# mainboard_v03.net
KiCad netlist of a schematic drawn in EAGLE
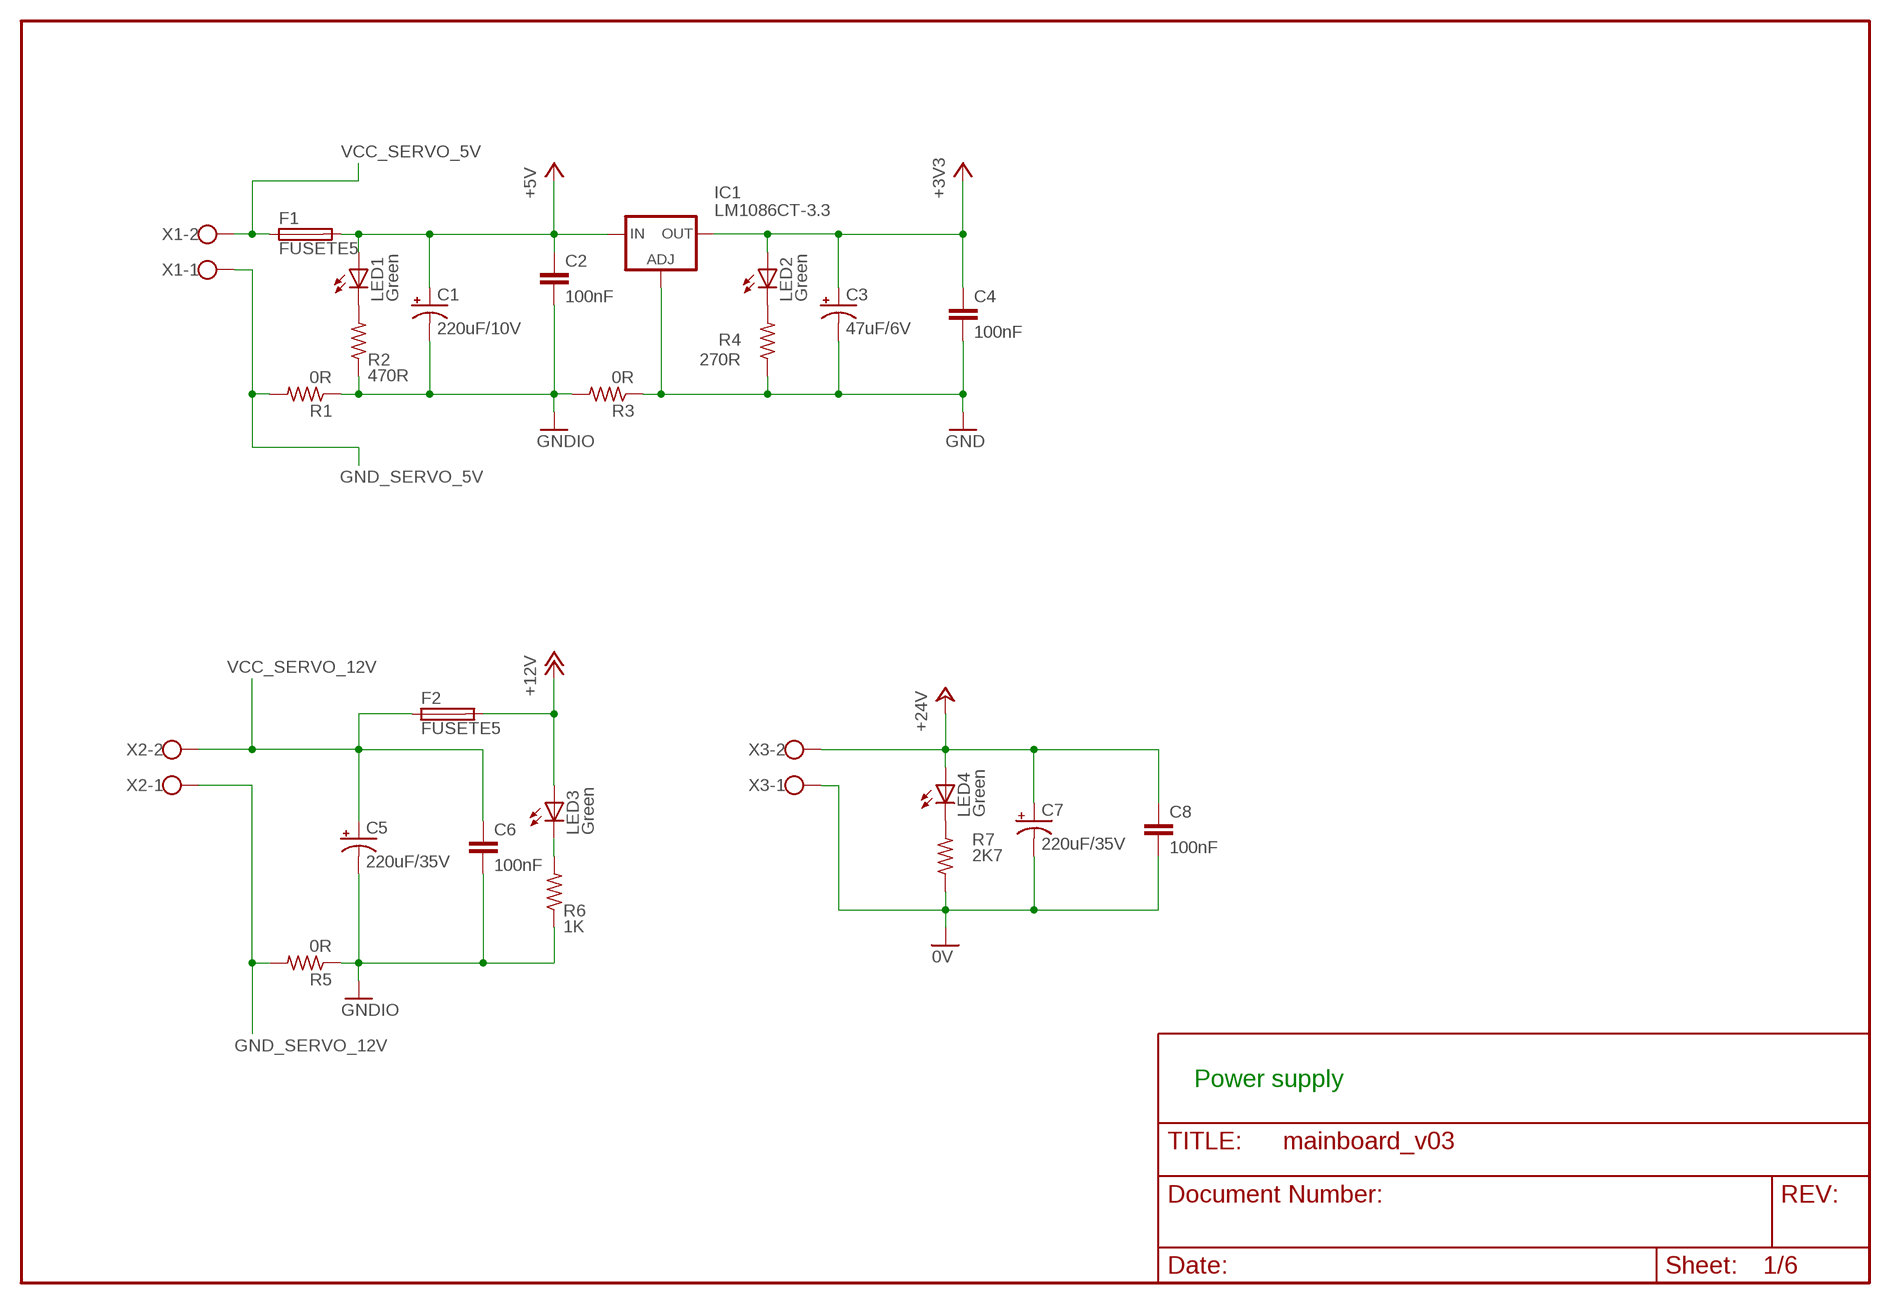
[diagram p0: schematic, sheet 1]
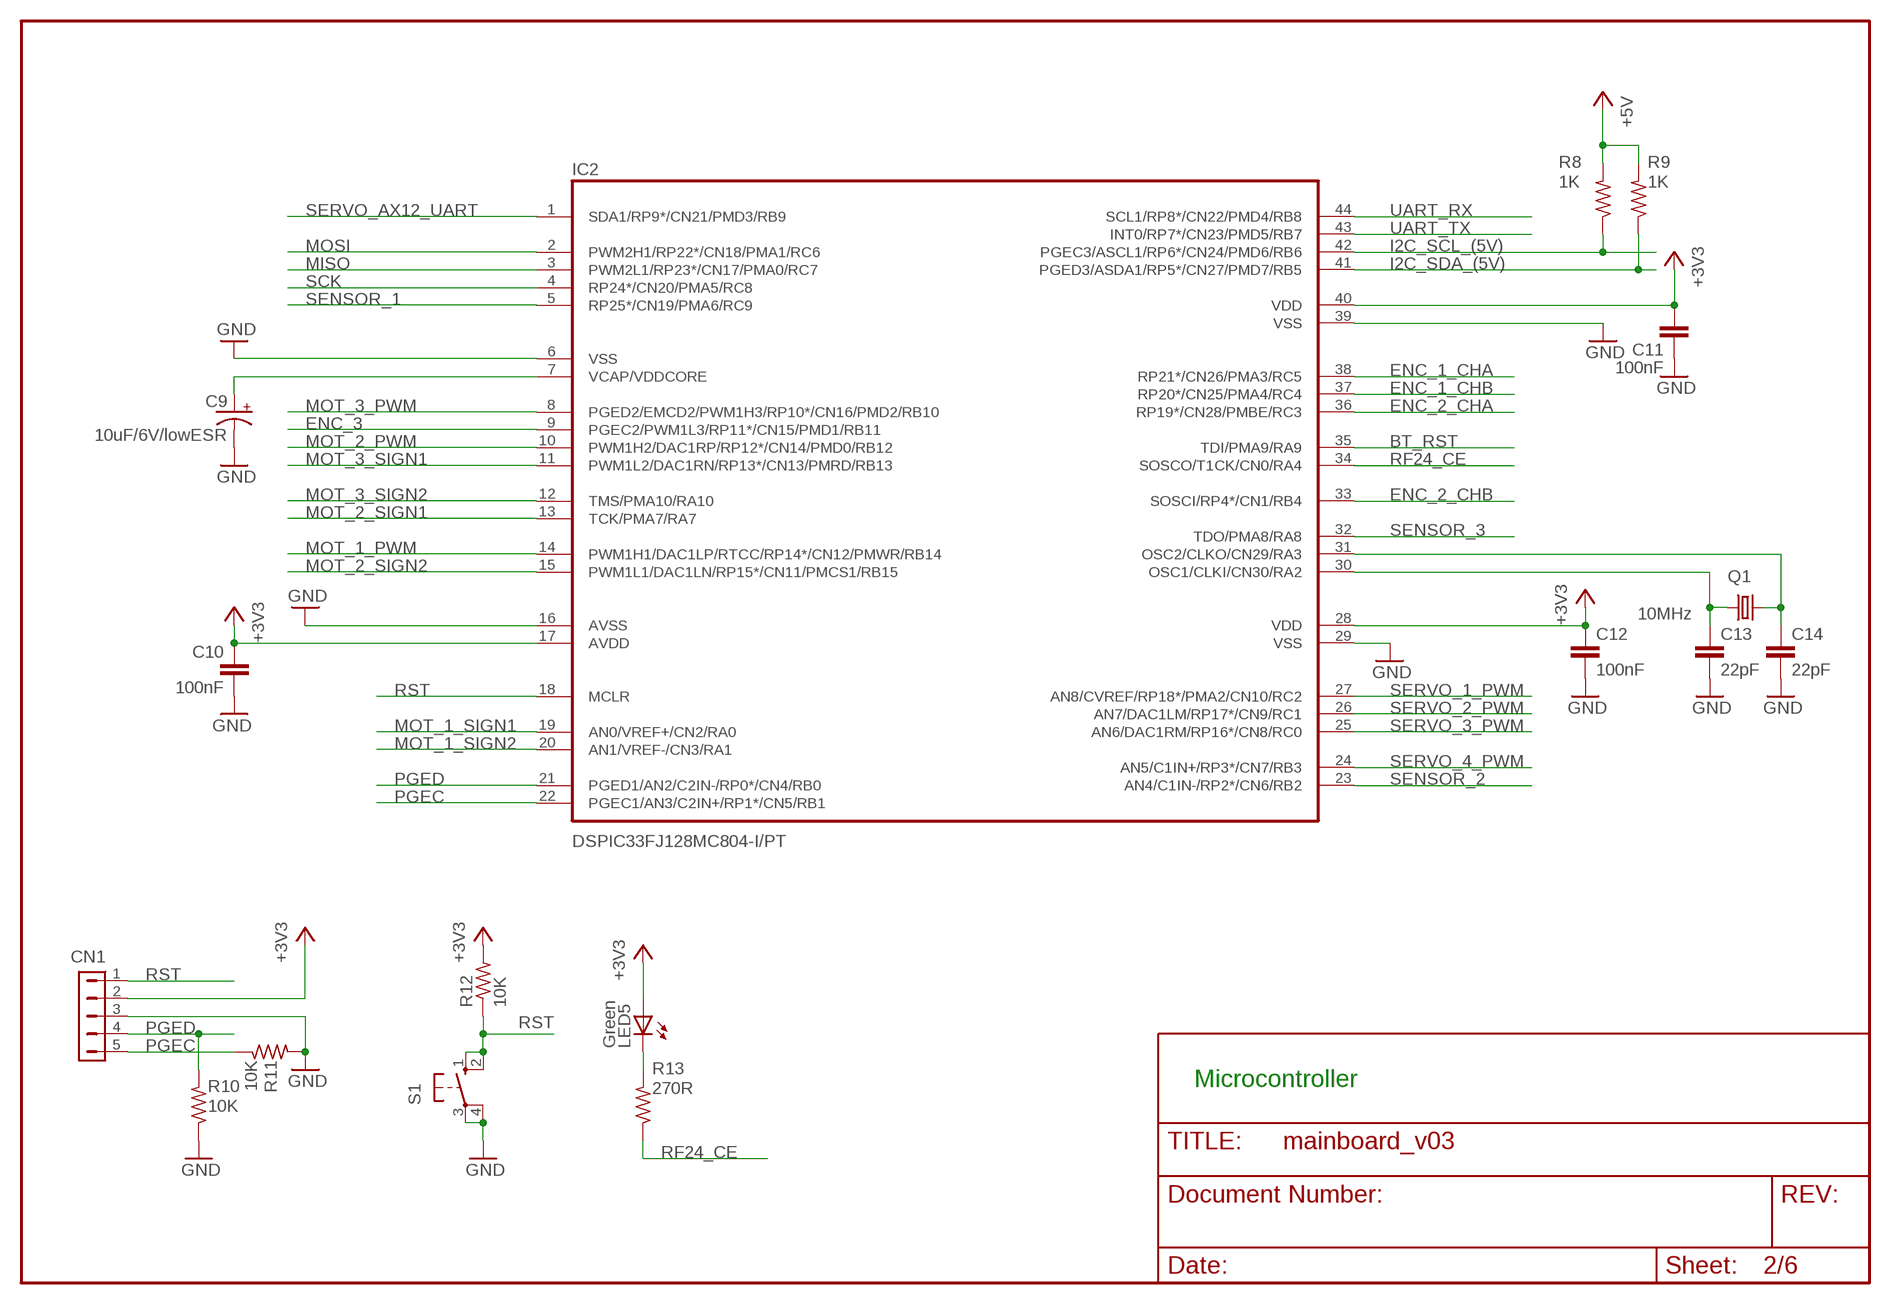
[diagram p1: schematic, sheet 2]
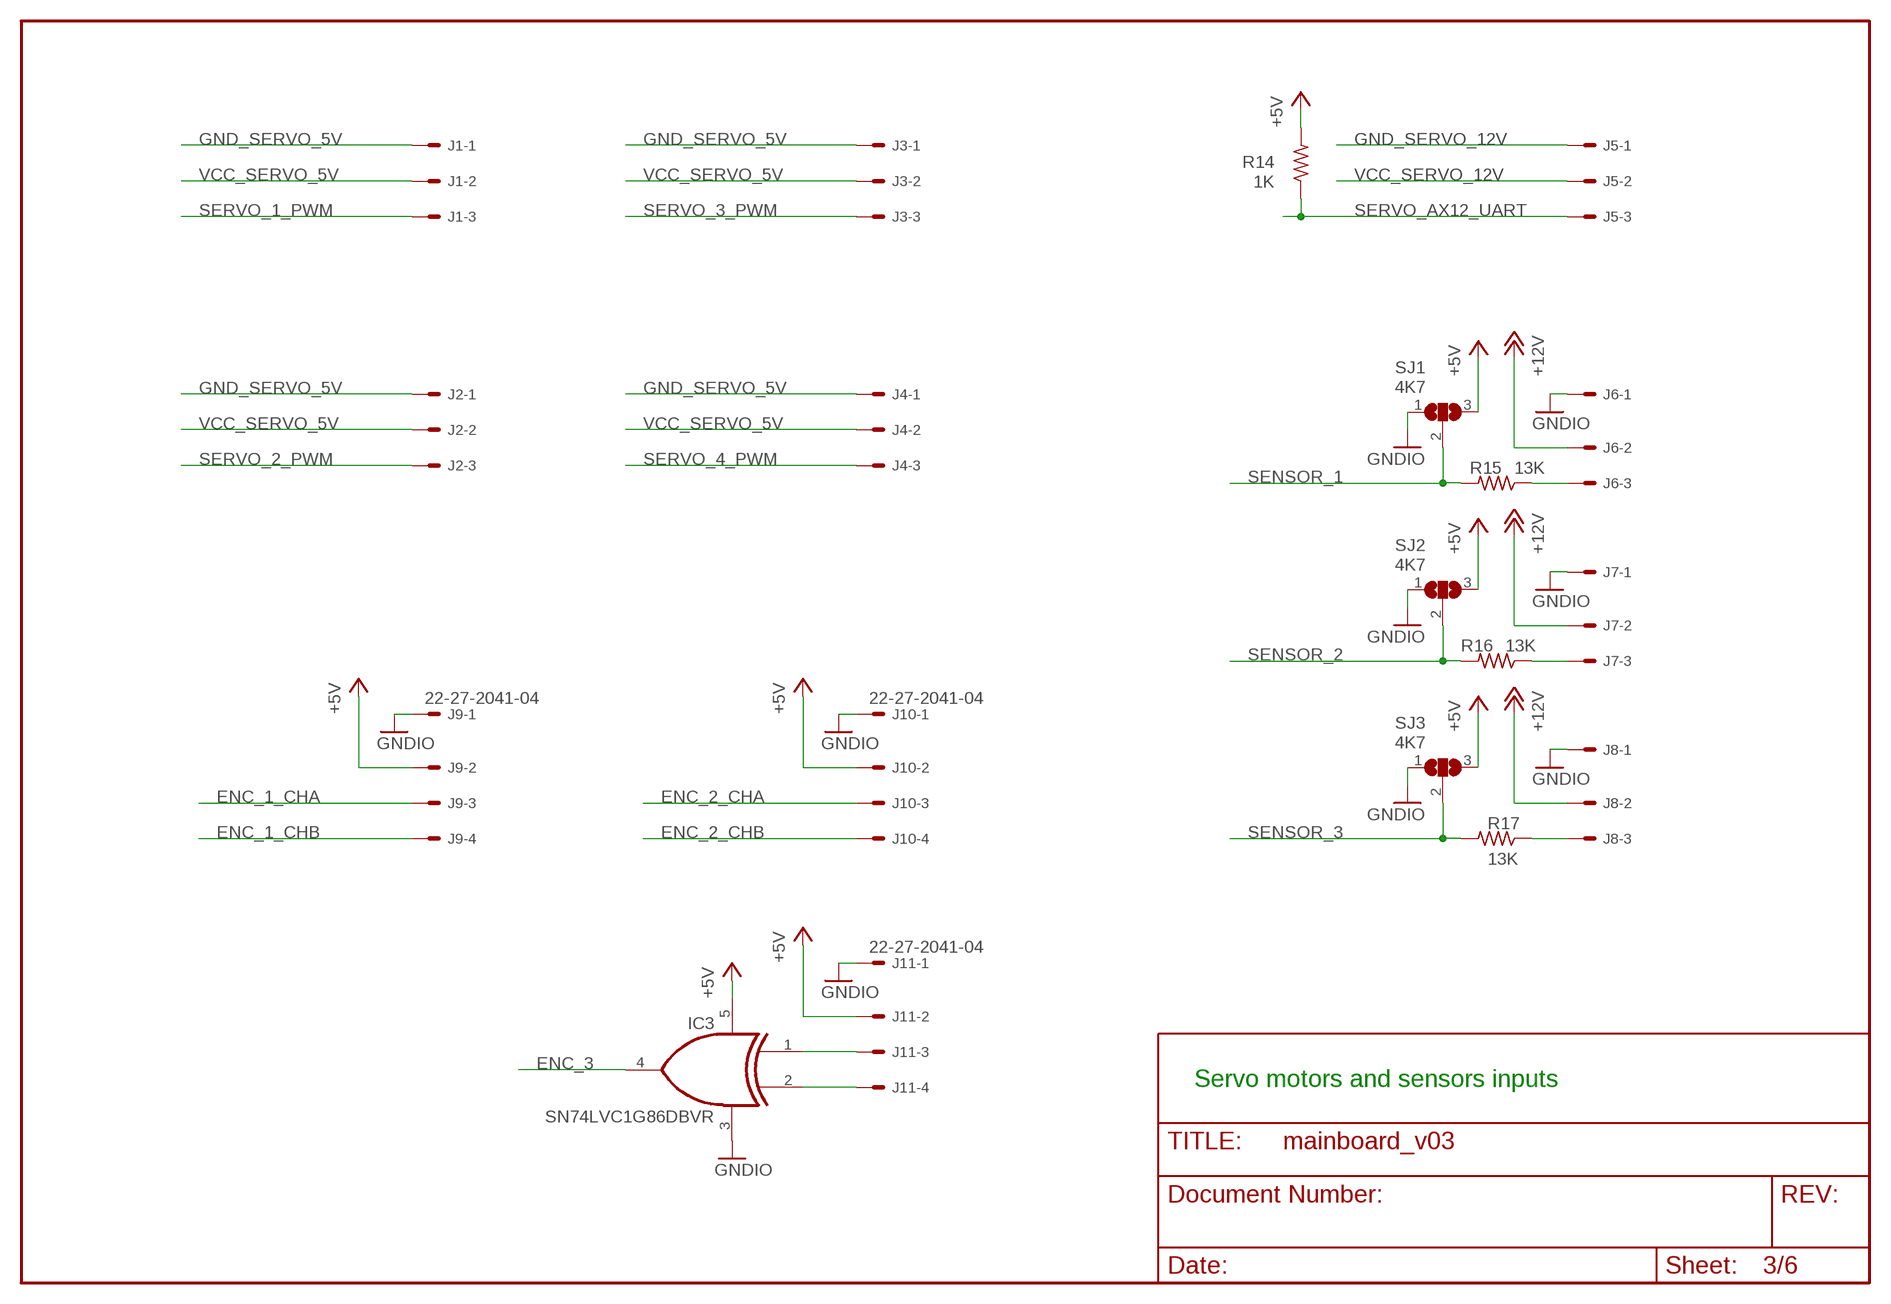
[diagram p2: schematic, sheet 3]
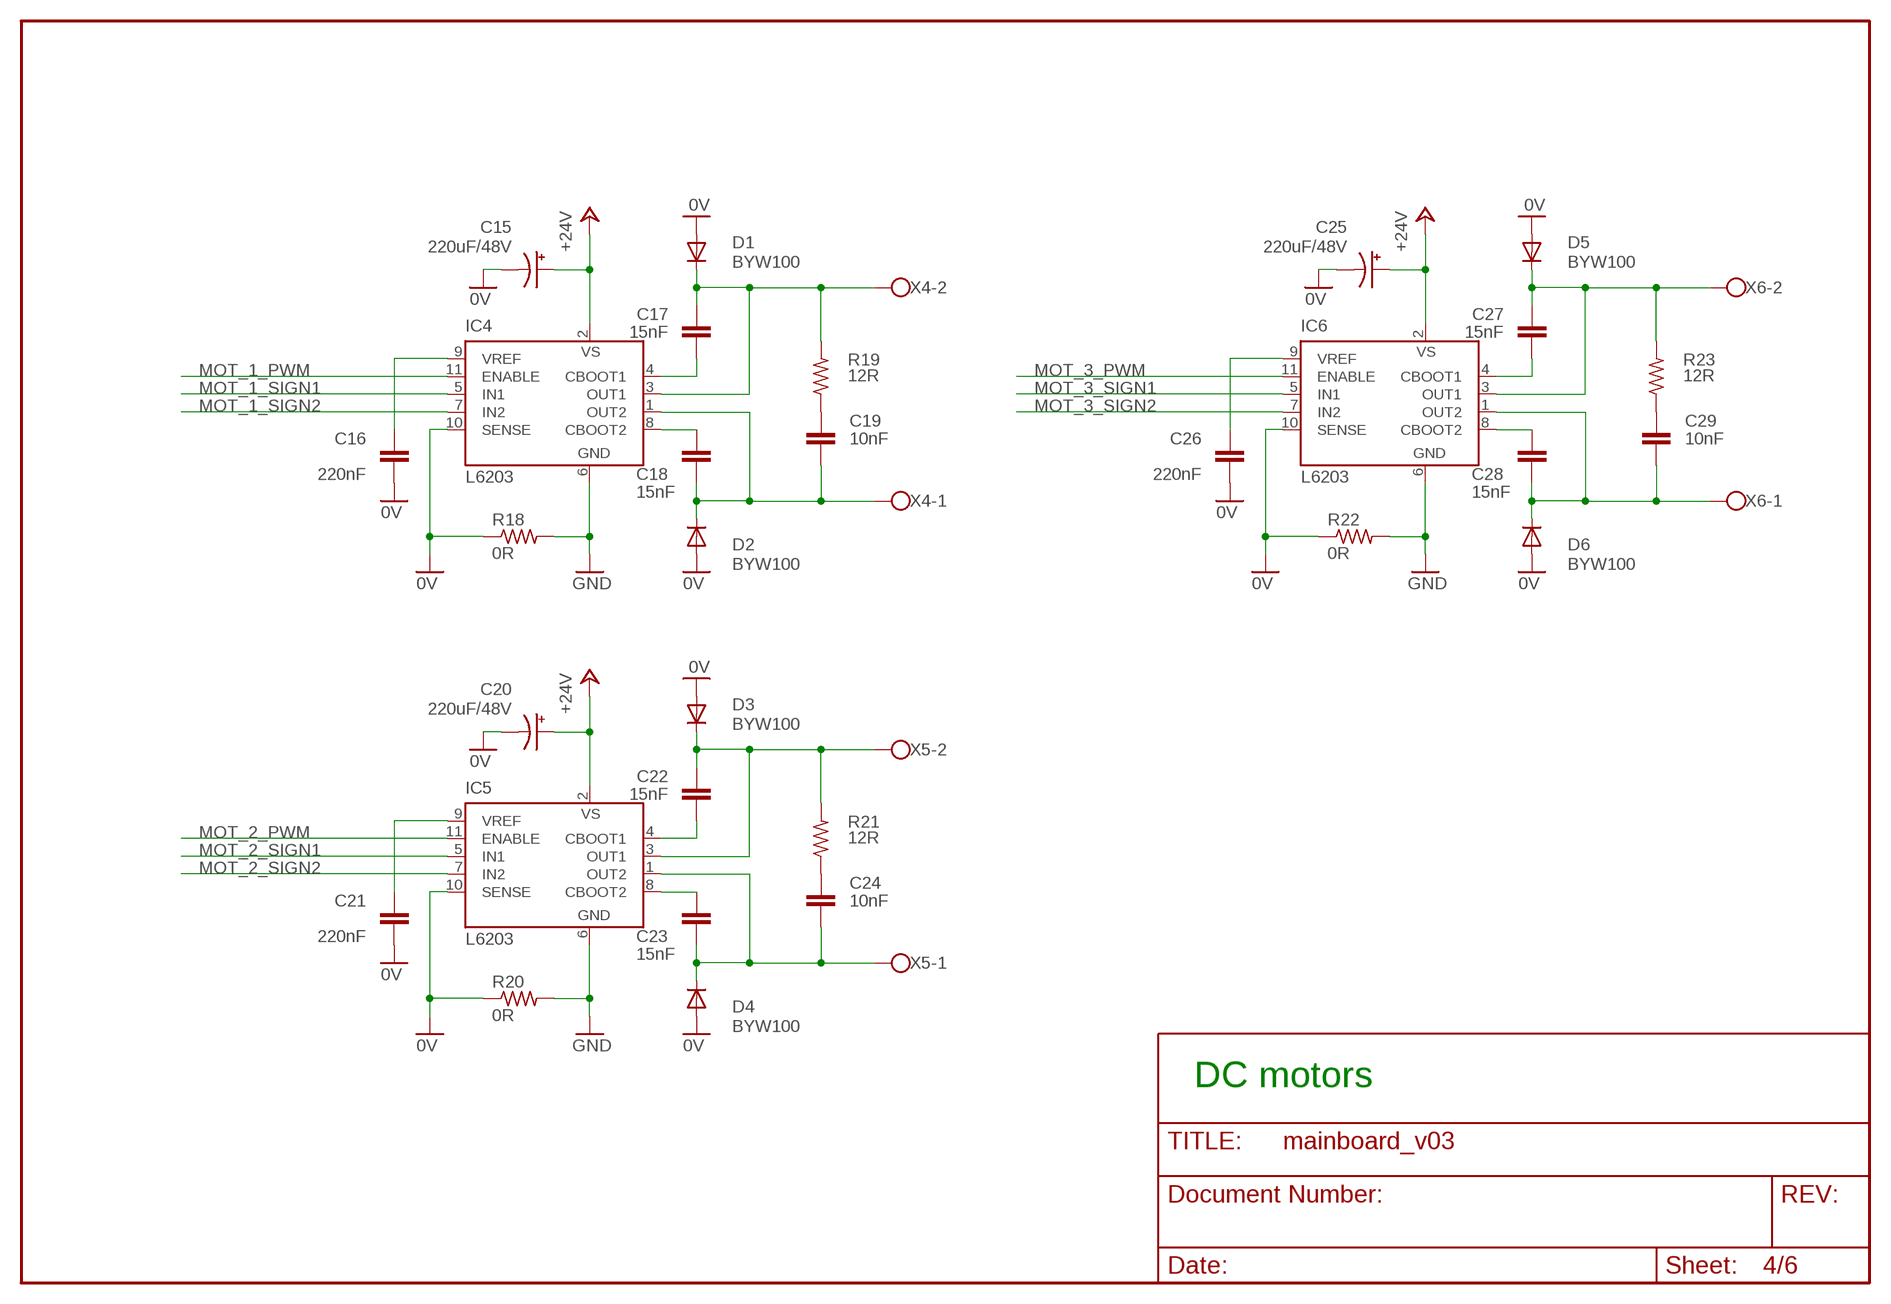
[diagram p3: schematic, sheet 4]
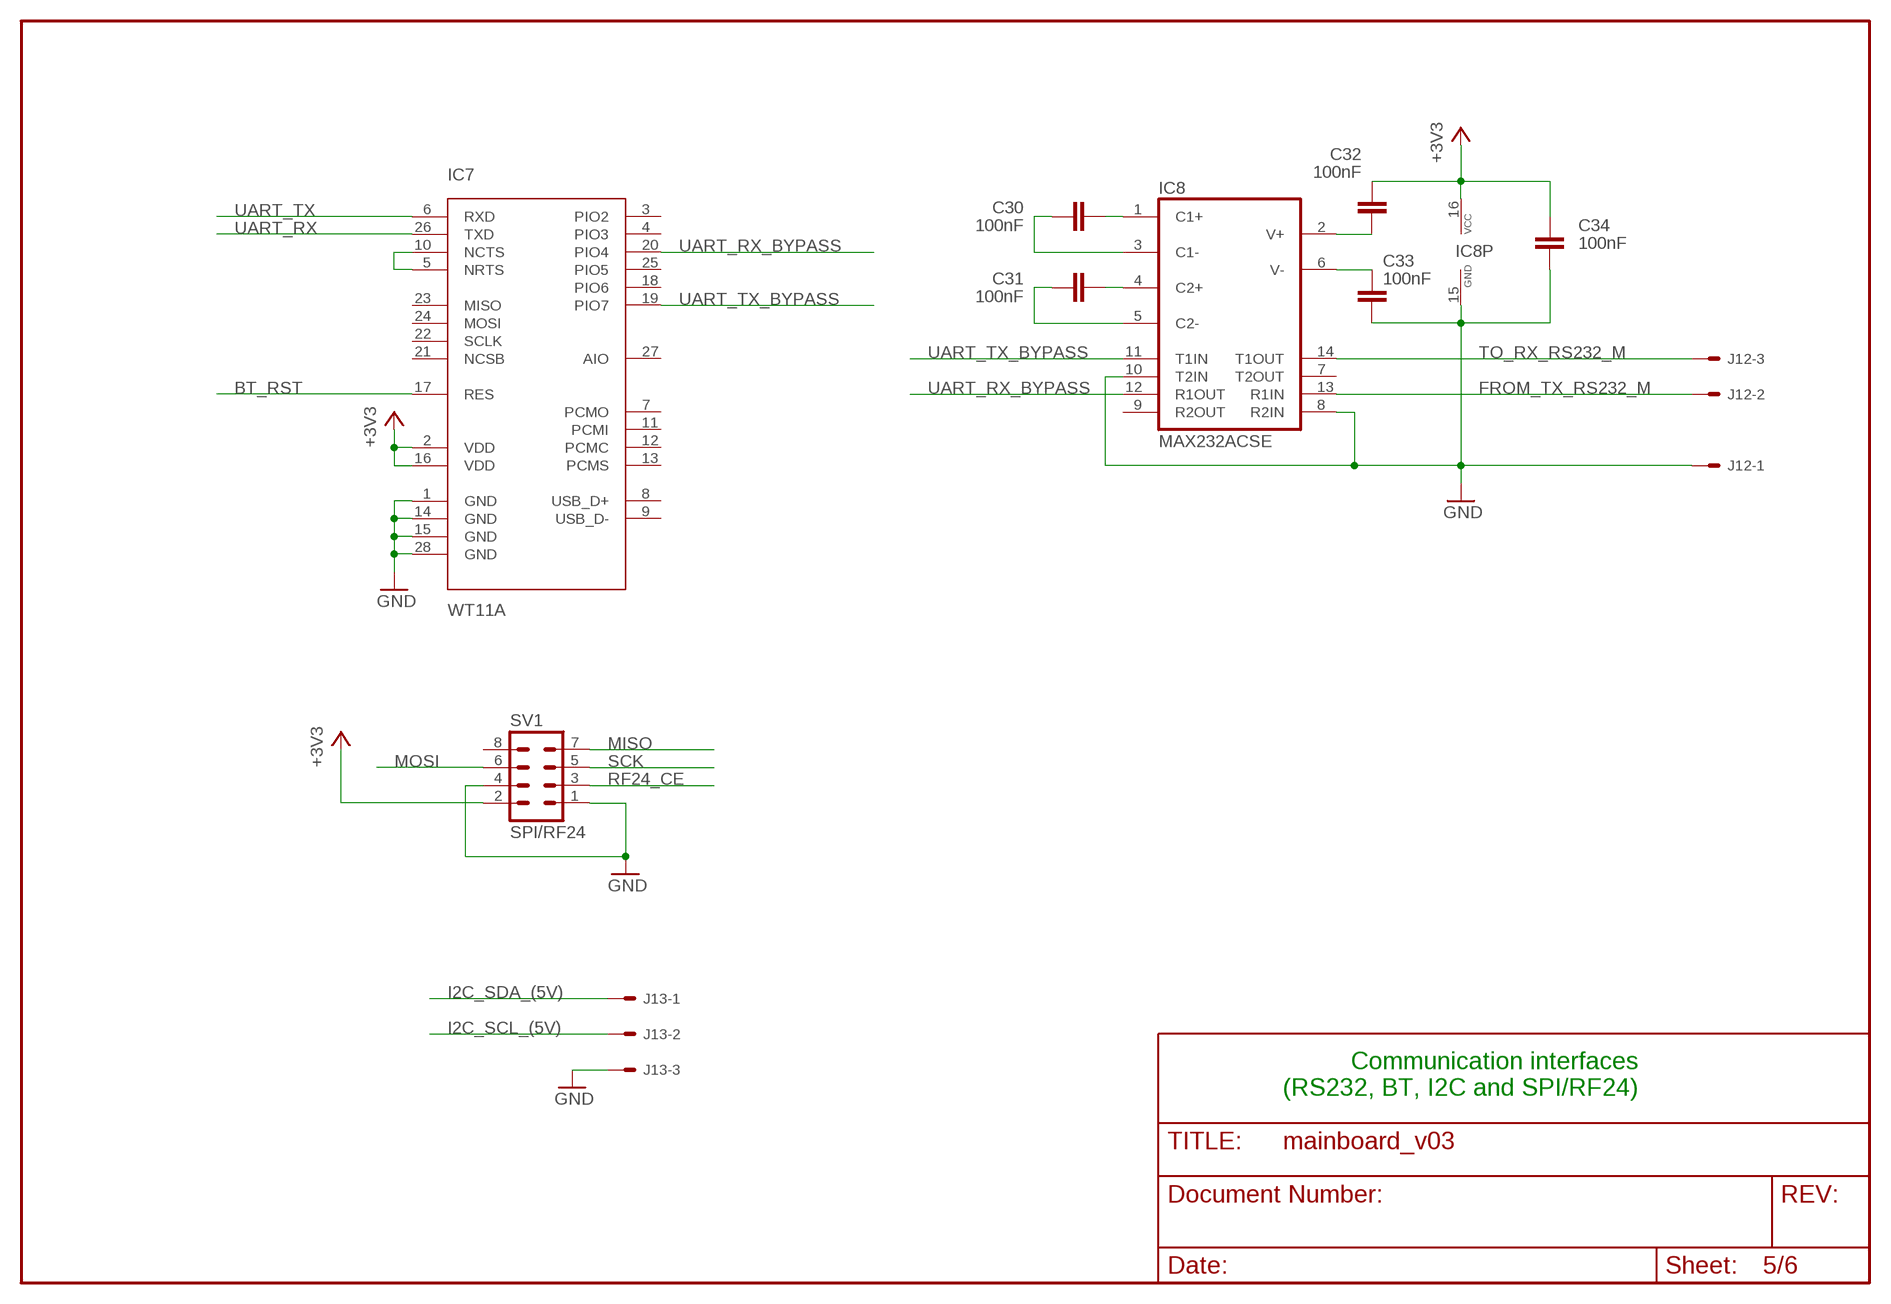
[diagram p4: schematic, sheet 5]
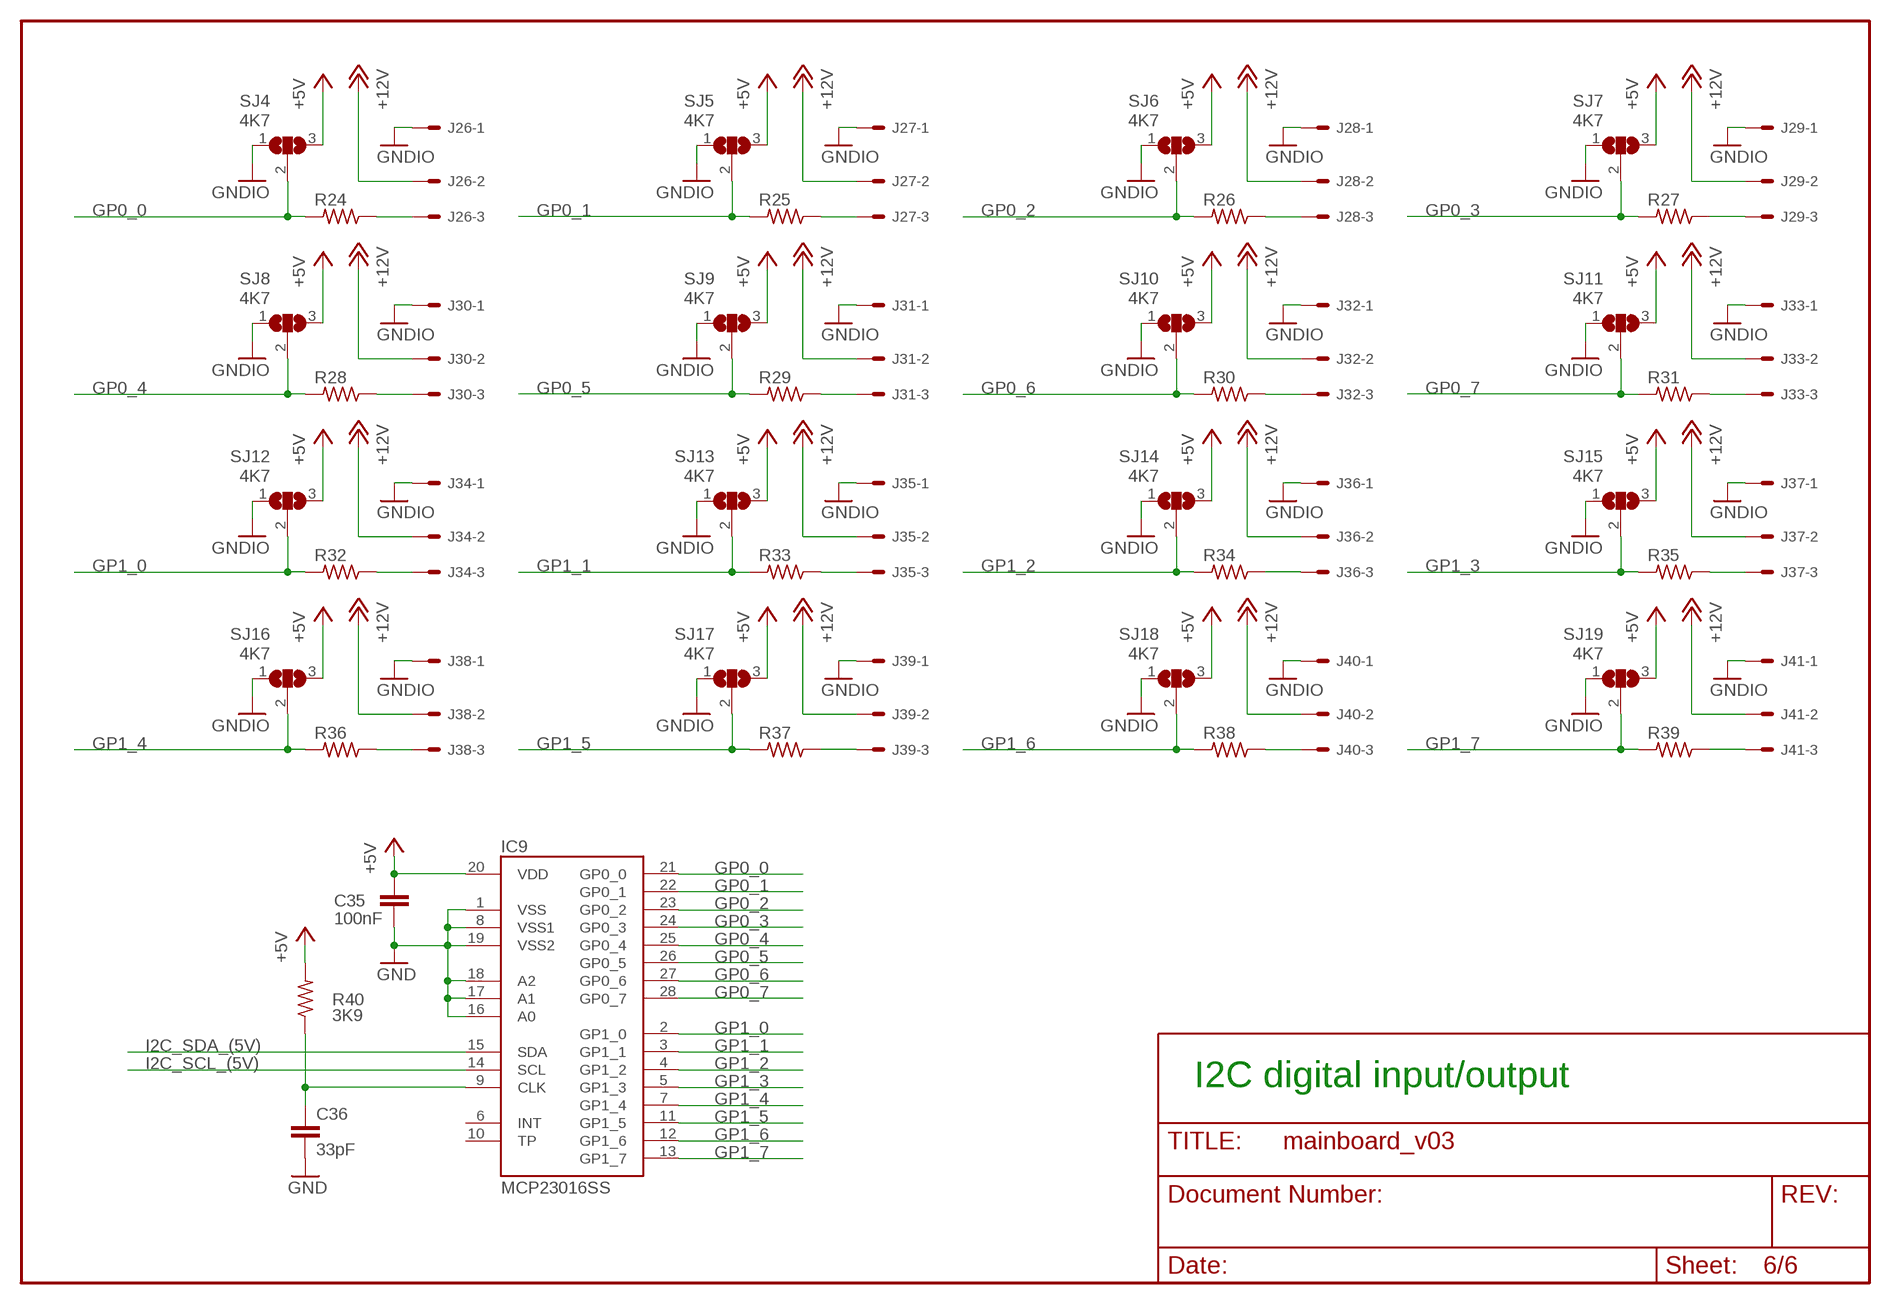
[diagram p5: schematic, sheet 6]

(export (version "E")
  (design (tool "Eeschema 10.0.6"))
  (components
    (comp (ref "C15")
      (value "220uF/48V")
      (footprint "eagle-import:E3,5-10")
      (libsource (lib "eagle-import") (part "CPOL-USE3.5-10"))
    )
    (comp (ref "C16")
      (value "220nF")
      (footprint "eagle-import:C0805")
      (libsource (lib "eagle-import") (part "C-EUC0805"))
    )
    (comp (ref "C17")
      (value "15nF")
      (footprint "eagle-import:C0805")
      (libsource (lib "eagle-import") (part "C-EUC0805"))
    )
    (comp (ref "C18")
      (value "15nF")
      (footprint "eagle-import:C0805")
      (libsource (lib "eagle-import") (part "C-EUC0805"))
    )
    (comp (ref "C19")
      (value "10nF")
      (footprint "eagle-import:C0805")
      (libsource (lib "eagle-import") (part "C-EUC0805"))
    )
    (comp (ref "C20")
      (value "220uF/48V")
      (footprint "eagle-import:E3,5-10")
      (libsource (lib "eagle-import") (part "CPOL-USE3.5-10"))
    )
    (comp (ref "C21")
      (value "220nF")
      (footprint "eagle-import:C0805")
      (libsource (lib "eagle-import") (part "C-EUC0805"))
    )
    (comp (ref "C22")
      (value "15nF")
      (footprint "eagle-import:C0805")
      (libsource (lib "eagle-import") (part "C-EUC0805"))
    )
    (comp (ref "C23")
      (value "15nF")
      (footprint "eagle-import:C0805")
      (libsource (lib "eagle-import") (part "C-EUC0805"))
    )
    (comp (ref "C24")
      (value "10nF")
      (footprint "eagle-import:C0805")
      (libsource (lib "eagle-import") (part "C-EUC0805"))
    )
    (comp (ref "C25")
      (value "220uF/48V")
      (footprint "eagle-import:E3,5-10")
      (libsource (lib "eagle-import") (part "CPOL-USE3.5-10"))
    )
    (comp (ref "C26")
      (value "220nF")
      (footprint "eagle-import:C0805")
      (libsource (lib "eagle-import") (part "C-EUC0805"))
    )
    (comp (ref "C27")
      (value "15nF")
      (footprint "eagle-import:C0805")
      (libsource (lib "eagle-import") (part "C-EUC0805"))
    )
    (comp (ref "C28")
      (value "15nF")
      (footprint "eagle-import:C0805")
      (libsource (lib "eagle-import") (part "C-EUC0805"))
    )
    (comp (ref "C29")
      (value "10nF")
      (footprint "eagle-import:C0805")
      (libsource (lib "eagle-import") (part "C-EUC0805"))
    )
    (comp (ref "D1")
      (value "BYW100")
      (footprint "eagle-import:F126-10")
      (libsource (lib "eagle-import") (part "BYW100"))
    )
    (comp (ref "D2")
      (value "BYW100")
      (footprint "eagle-import:F126-10")
      (libsource (lib "eagle-import") (part "BYW100"))
    )
    (comp (ref "D3")
      (value "BYW100")
      (footprint "eagle-import:F126-10")
      (libsource (lib "eagle-import") (part "BYW100"))
    )
    (comp (ref "D4")
      (value "BYW100")
      (footprint "eagle-import:F126-10")
      (libsource (lib "eagle-import") (part "BYW100"))
    )
    (comp (ref "D5")
      (value "BYW100")
      (footprint "eagle-import:F126-10")
      (libsource (lib "eagle-import") (part "BYW100"))
    )
    (comp (ref "D6")
      (value "BYW100")
      (footprint "eagle-import:F126-10")
      (libsource (lib "eagle-import") (part "BYW100"))
    )
    (comp (ref "IC4")
      (value "L6203")
      (footprint "eagle-import:MULTIWATT-11")
      (libsource (lib "eagle-import") (part "L6203"))
    )
    (comp (ref "IC5")
      (value "L6203")
      (footprint "eagle-import:MULTIWATT-11")
      (libsource (lib "eagle-import") (part "L6203"))
    )
    (comp (ref "IC6")
      (value "L6203")
      (footprint "eagle-import:MULTIWATT-11")
      (libsource (lib "eagle-import") (part "L6203"))
    )
    (comp (ref "R18")
      (value "0R")
      (footprint "eagle-import:M0805")
      (libsource (lib "eagle-import") (part "R-US_M0805"))
    )
    (comp (ref "R19")
      (value "12R")
      (footprint "eagle-import:M0805")
      (libsource (lib "eagle-import") (part "R-US_M0805"))
    )
    (comp (ref "R20")
      (value "0R")
      (footprint "eagle-import:M0805")
      (libsource (lib "eagle-import") (part "R-US_M0805"))
    )
    (comp (ref "R21")
      (value "12R")
      (footprint "eagle-import:M0805")
      (libsource (lib "eagle-import") (part "R-US_M0805"))
    )
    (comp (ref "R22")
      (value "0R")
      (footprint "eagle-import:M0805")
      (libsource (lib "eagle-import") (part "R-US_M0805"))
    )
    (comp (ref "R23")
      (value "12R")
      (footprint "eagle-import:M0805")
      (libsource (lib "eagle-import") (part "R-US_M0805"))
    )
    (comp (ref "X4")
      (value "W237-02P")
      (footprint "eagle-import:W237-132")
      (libsource (lib "eagle-import") (part "W237-02P"))
    )
    (comp (ref "X5")
      (value "W237-02P")
      (footprint "eagle-import:W237-132")
      (libsource (lib "eagle-import") (part "W237-02P"))
    )
    (comp (ref "X6")
      (value "W237-02P")
      (footprint "eagle-import:W237-132")
      (libsource (lib "eagle-import") (part "W237-02P"))
    )
    (comp (ref "IC3")
      (value "SN74LVC1G86DBVR")
      (footprint "eagle-import:SOT23-5")
      (libsource (lib "eagle-import") (part "741G86DBVAHC"))
    )
    (comp (ref "J1")
      (value "22-27-2031-03")
      (footprint "eagle-import:6410-03")
      (libsource (lib "eagle-import") (part "22-?-0327-2031"))
    )
    (comp (ref "J2")
      (value "22-27-2031-03")
      (footprint "eagle-import:6410-03")
      (libsource (lib "eagle-import") (part "22-?-0327-2031"))
    )
    (comp (ref "J3")
      (value "22-27-2031-03")
      (footprint "eagle-import:6410-03")
      (libsource (lib "eagle-import") (part "22-?-0327-2031"))
    )
    (comp (ref "J4")
      (value "22-27-2031-03")
      (footprint "eagle-import:6410-03")
      (libsource (lib "eagle-import") (part "22-?-0327-2031"))
    )
    (comp (ref "J5")
      (value "22-27-2031-03")
      (footprint "eagle-import:6410-03")
      (libsource (lib "eagle-import") (part "22-?-0327-2031"))
    )
    (comp (ref "J6")
      (value "22-27-2031-03")
      (footprint "eagle-import:6410-03")
      (libsource (lib "eagle-import") (part "22-?-0327-2031"))
    )
    (comp (ref "J7")
      (value "22-27-2031-03")
      (footprint "eagle-import:6410-03")
      (libsource (lib "eagle-import") (part "22-?-0327-2031"))
    )
    (comp (ref "J8")
      (value "22-27-2031-03")
      (footprint "eagle-import:6410-03")
      (libsource (lib "eagle-import") (part "22-?-0327-2031"))
    )
    (comp (ref "J9")
      (value "22-27-2041-04")
      (footprint "eagle-import:6410-04")
      (libsource (lib "eagle-import") (part "22-?-0427-2041"))
    )
    (comp (ref "J10")
      (value "22-27-2041-04")
      (footprint "eagle-import:6410-04")
      (libsource (lib "eagle-import") (part "22-?-0427-2041"))
    )
    (comp (ref "J11")
      (value "22-27-2041-04")
      (footprint "eagle-import:6410-04")
      (libsource (lib "eagle-import") (part "22-?-0427-2041"))
    )
    (comp (ref "R14")
      (value "1K")
      (footprint "eagle-import:R0805")
      (libsource (lib "eagle-import") (part "R-US_R0805"))
    )
    (comp (ref "R15")
      (value "13K")
      (footprint "eagle-import:R0805")
      (libsource (lib "eagle-import") (part "R-US_R0805"))
    )
    (comp (ref "R16")
      (value "13K")
      (footprint "eagle-import:R0805")
      (libsource (lib "eagle-import") (part "R-US_R0805"))
    )
    (comp (ref "R17")
      (value "13K")
      (footprint "eagle-import:R0805")
      (libsource (lib "eagle-import") (part "R-US_R0805"))
    )
    (comp (ref "SJ1")
      (value "4K7")
      (footprint "eagle-import:SJ_2")
      (libsource (lib "eagle-import") (part "SJ2W"))
    )
    (comp (ref "SJ2")
      (value "4K7")
      (footprint "eagle-import:SJ_2")
      (libsource (lib "eagle-import") (part "SJ2W"))
    )
    (comp (ref "SJ3")
      (value "4K7")
      (footprint "eagle-import:SJ_2")
      (libsource (lib "eagle-import") (part "SJ2W"))
    )
    (comp (ref "C30")
      (value "100nF")
      (footprint "eagle-import:C0603")
      (libsource (lib "eagle-import") (part "C-EUC0603"))
    )
    (comp (ref "C31")
      (value "100nF")
      (footprint "eagle-import:C0603")
      (libsource (lib "eagle-import") (part "C-EUC0603"))
    )
    (comp (ref "C32")
      (value "100nF")
      (footprint "eagle-import:C0603")
      (libsource (lib "eagle-import") (part "C-EUC0603"))
    )
    (comp (ref "C33")
      (value "100nF")
      (footprint "eagle-import:C0603")
      (libsource (lib "eagle-import") (part "C-EUC0603"))
    )
    (comp (ref "C34")
      (value "100nF")
      (footprint "eagle-import:C0603")
      (libsource (lib "eagle-import") (part "C-EUC0603"))
    )
    (comp (ref "IC7")
      (value "WT11A")
      (footprint "eagle-import:WT11")
      (libsource (lib "eagle-import") (part "WT11A"))
    )
    (comp (ref "IC8")
      (value "MAX232ACSE")
      (footprint "eagle-import:SO16")
      (libsource (lib "eagle-import") (part "MAX232SEAC"))
    )
    (comp (ref "J12")
      (value "22-27-2031-03")
      (footprint "eagle-import:6410-03")
      (libsource (lib "eagle-import") (part "22-?-0327-2031"))
    )
    (comp (ref "J13")
      (value "22-27-2031-03")
      (footprint "eagle-import:6410-03")
      (libsource (lib "eagle-import") (part "22-?-0327-2031"))
    )
    (comp (ref "SV1")
      (value "SPI/RF24")
      (footprint "eagle-import:MA04-2")
      (libsource (lib "eagle-import") (part "MA04-2"))
    )
    (comp (ref "C35")
      (value "100nF")
      (footprint "eagle-import:C0805")
      (libsource (lib "eagle-import") (part "C-EUC0805"))
    )
    (comp (ref "C36")
      (value "33pF")
      (footprint "eagle-import:C0805")
      (libsource (lib "eagle-import") (part "C-EUC0805"))
    )
    (comp (ref "IC9")
      (value "MCP23016SS")
      (footprint "eagle-import:SSOP28")
      (libsource (lib "eagle-import") (part "MCP23016SS"))
    )
    (comp (ref "J26")
      (value "22-27-2031-03")
      (footprint "eagle-import:6410-03")
      (libsource (lib "eagle-import") (part "22-?-0327-2031"))
    )
    (comp (ref "J27")
      (value "22-27-2031-03")
      (footprint "eagle-import:6410-03")
      (libsource (lib "eagle-import") (part "22-?-0327-2031"))
    )
    (comp (ref "J28")
      (value "22-27-2031-03")
      (footprint "eagle-import:6410-03")
      (libsource (lib "eagle-import") (part "22-?-0327-2031"))
    )
    (comp (ref "J29")
      (value "22-27-2031-03")
      (footprint "eagle-import:6410-03")
      (libsource (lib "eagle-import") (part "22-?-0327-2031"))
    )
    (comp (ref "J30")
      (value "22-27-2031-03")
      (footprint "eagle-import:6410-03")
      (libsource (lib "eagle-import") (part "22-?-0327-2031"))
    )
    (comp (ref "J31")
      (value "22-27-2031-03")
      (footprint "eagle-import:6410-03")
      (libsource (lib "eagle-import") (part "22-?-0327-2031"))
    )
    (comp (ref "J32")
      (value "22-27-2031-03")
      (footprint "eagle-import:6410-03")
      (libsource (lib "eagle-import") (part "22-?-0327-2031"))
    )
    (comp (ref "J33")
      (value "22-27-2031-03")
      (footprint "eagle-import:6410-03")
      (libsource (lib "eagle-import") (part "22-?-0327-2031"))
    )
    (comp (ref "J34")
      (value "22-27-2031-03")
      (footprint "eagle-import:6410-03")
      (libsource (lib "eagle-import") (part "22-?-0327-2031"))
    )
    (comp (ref "J35")
      (value "22-27-2031-03")
      (footprint "eagle-import:6410-03")
      (libsource (lib "eagle-import") (part "22-?-0327-2031"))
    )
    (comp (ref "J36")
      (value "22-27-2031-03")
      (footprint "eagle-import:6410-03")
      (libsource (lib "eagle-import") (part "22-?-0327-2031"))
    )
    (comp (ref "J37")
      (value "22-27-2031-03")
      (footprint "eagle-import:6410-03")
      (libsource (lib "eagle-import") (part "22-?-0327-2031"))
    )
    (comp (ref "J38")
      (value "22-27-2031-03")
      (footprint "eagle-import:6410-03")
      (libsource (lib "eagle-import") (part "22-?-0327-2031"))
    )
    (comp (ref "J39")
      (value "22-27-2031-03")
      (footprint "eagle-import:6410-03")
      (libsource (lib "eagle-import") (part "22-?-0327-2031"))
    )
    (comp (ref "J40")
      (value "22-27-2031-03")
      (footprint "eagle-import:6410-03")
      (libsource (lib "eagle-import") (part "22-?-0327-2031"))
    )
    (comp (ref "J41")
      (value "22-27-2031-03")
      (footprint "eagle-import:6410-03")
      (libsource (lib "eagle-import") (part "22-?-0327-2031"))
    )
    (comp (ref "R24")
      (value "R-US_R0805")
      (footprint "eagle-import:R0805")
      (libsource (lib "eagle-import") (part "R-US_R0805"))
    )
    (comp (ref "R25")
      (value "R-US_R0805")
      (footprint "eagle-import:R0805")
      (libsource (lib "eagle-import") (part "R-US_R0805"))
    )
    (comp (ref "R26")
      (value "R-US_R0805")
      (footprint "eagle-import:R0805")
      (libsource (lib "eagle-import") (part "R-US_R0805"))
    )
    (comp (ref "R27")
      (value "R-US_R0805")
      (footprint "eagle-import:R0805")
      (libsource (lib "eagle-import") (part "R-US_R0805"))
    )
    (comp (ref "R28")
      (value "R-US_R0805")
      (footprint "eagle-import:R0805")
      (libsource (lib "eagle-import") (part "R-US_R0805"))
    )
    (comp (ref "R29")
      (value "R-US_R0805")
      (footprint "eagle-import:R0805")
      (libsource (lib "eagle-import") (part "R-US_R0805"))
    )
    (comp (ref "R30")
      (value "R-US_R0805")
      (footprint "eagle-import:R0805")
      (libsource (lib "eagle-import") (part "R-US_R0805"))
    )
    (comp (ref "R31")
      (value "R-US_R0805")
      (footprint "eagle-import:R0805")
      (libsource (lib "eagle-import") (part "R-US_R0805"))
    )
    (comp (ref "R32")
      (value "R-US_R0805")
      (footprint "eagle-import:R0805")
      (libsource (lib "eagle-import") (part "R-US_R0805"))
    )
    (comp (ref "R33")
      (value "R-US_R0805")
      (footprint "eagle-import:R0805")
      (libsource (lib "eagle-import") (part "R-US_R0805"))
    )
    (comp (ref "R34")
      (value "R-US_R0805")
      (footprint "eagle-import:R0805")
      (libsource (lib "eagle-import") (part "R-US_R0805"))
    )
    (comp (ref "R35")
      (value "R-US_R0805")
      (footprint "eagle-import:R0805")
      (libsource (lib "eagle-import") (part "R-US_R0805"))
    )
    (comp (ref "R36")
      (value "R-US_R0805")
      (footprint "eagle-import:R0805")
      (libsource (lib "eagle-import") (part "R-US_R0805"))
    )
    (comp (ref "R37")
      (value "R-US_R0805")
      (footprint "eagle-import:R0805")
      (libsource (lib "eagle-import") (part "R-US_R0805"))
    )
    (comp (ref "R38")
      (value "R-US_R0805")
      (footprint "eagle-import:R0805")
      (libsource (lib "eagle-import") (part "R-US_R0805"))
    )
    (comp (ref "R39")
      (value "R-US_R0805")
      (footprint "eagle-import:R0805")
      (libsource (lib "eagle-import") (part "R-US_R0805"))
    )
    (comp (ref "R40")
      (value "3K9")
      (footprint "eagle-import:R0805")
      (libsource (lib "eagle-import") (part "R-US_R0805"))
    )
    (comp (ref "SJ4")
      (value "4K7")
      (footprint "eagle-import:SJ_2")
      (libsource (lib "eagle-import") (part "SJ2W"))
    )
    (comp (ref "SJ5")
      (value "4K7")
      (footprint "eagle-import:SJ_2")
      (libsource (lib "eagle-import") (part "SJ2W"))
    )
    (comp (ref "SJ6")
      (value "4K7")
      (footprint "eagle-import:SJ_2")
      (libsource (lib "eagle-import") (part "SJ2W"))
    )
    (comp (ref "SJ7")
      (value "4K7")
      (footprint "eagle-import:SJ_2")
      (libsource (lib "eagle-import") (part "SJ2W"))
    )
    (comp (ref "SJ8")
      (value "4K7")
      (footprint "eagle-import:SJ_2")
      (libsource (lib "eagle-import") (part "SJ2W"))
    )
    (comp (ref "SJ9")
      (value "4K7")
      (footprint "eagle-import:SJ_2")
      (libsource (lib "eagle-import") (part "SJ2W"))
    )
    (comp (ref "SJ10")
      (value "4K7")
      (footprint "eagle-import:SJ_2")
      (libsource (lib "eagle-import") (part "SJ2W"))
    )
    (comp (ref "SJ11")
      (value "4K7")
      (footprint "eagle-import:SJ_2")
      (libsource (lib "eagle-import") (part "SJ2W"))
    )
    (comp (ref "SJ12")
      (value "4K7")
      (footprint "eagle-import:SJ_2")
      (libsource (lib "eagle-import") (part "SJ2W"))
    )
    (comp (ref "SJ13")
      (value "4K7")
      (footprint "eagle-import:SJ_2")
      (libsource (lib "eagle-import") (part "SJ2W"))
    )
    (comp (ref "SJ14")
      (value "4K7")
      (footprint "eagle-import:SJ_2")
      (libsource (lib "eagle-import") (part "SJ2W"))
    )
    (comp (ref "SJ15")
      (value "4K7")
      (footprint "eagle-import:SJ_2")
      (libsource (lib "eagle-import") (part "SJ2W"))
    )
    (comp (ref "SJ16")
      (value "4K7")
      (footprint "eagle-import:SJ_2")
      (libsource (lib "eagle-import") (part "SJ2W"))
    )
    (comp (ref "SJ17")
      (value "4K7")
      (footprint "eagle-import:SJ_2")
      (libsource (lib "eagle-import") (part "SJ2W"))
    )
    (comp (ref "SJ18")
      (value "4K7")
      (footprint "eagle-import:SJ_2")
      (libsource (lib "eagle-import") (part "SJ2W"))
    )
    (comp (ref "SJ19")
      (value "4K7")
      (footprint "eagle-import:SJ_2")
      (libsource (lib "eagle-import") (part "SJ2W"))
    )
    (comp (ref "C1")
      (value "220uF/10V")
      (footprint "eagle-import:E2,5-7")
      (libsource (lib "eagle-import") (part "CPOL-USE2.5-7"))
    )
    (comp (ref "C2")
      (value "100nF")
      (footprint "eagle-import:C0805")
      (libsource (lib "eagle-import") (part "C-EUC0805"))
    )
    (comp (ref "C3")
      (value "47uF/6V")
      (footprint "eagle-import:SMC_D")
      (libsource (lib "eagle-import") (part "CPOL-USSMCD"))
    )
    (comp (ref "C4")
      (value "100nF")
      (footprint "eagle-import:C0805")
      (libsource (lib "eagle-import") (part "C-EUC0805"))
    )
    (comp (ref "C5")
      (value "220uF/35V")
      (footprint "eagle-import:E5-10,5")
      (libsource (lib "eagle-import") (part "CPOL-USE5-10.5"))
    )
    (comp (ref "C6")
      (value "100nF")
      (footprint "eagle-import:C0805")
      (libsource (lib "eagle-import") (part "C-EUC0805"))
    )
    (comp (ref "C7")
      (value "220uF/35V")
      (footprint "eagle-import:E5-10,5")
      (libsource (lib "eagle-import") (part "CPOL-USE5-10.5"))
    )
    (comp (ref "C8")
      (value "100nF")
      (footprint "eagle-import:C0805")
      (libsource (lib "eagle-import") (part "C-EUC0805"))
    )
    (comp (ref "F1")
      (value "FUSETE5")
      (footprint "eagle-import:TE5")
      (libsource (lib "eagle-import") (part "FUSETE5"))
    )
    (comp (ref "F2")
      (value "FUSETE5")
      (footprint "eagle-import:TE5")
      (libsource (lib "eagle-import") (part "FUSETE5"))
    )
    (comp (ref "IC1")
      (value "LM1086CT-3.3")
      (footprint "eagle-import:317TS")
      (libsource (lib "eagle-import") (part "LM317TS"))
    )
    (comp (ref "LED1")
      (value "Green")
      (footprint "eagle-import:CHIP-LED0805")
      (libsource (lib "eagle-import") (part "LEDCHIP-LED0805"))
    )
    (comp (ref "LED2")
      (value "Green")
      (footprint "eagle-import:CHIP-LED0805")
      (libsource (lib "eagle-import") (part "LEDCHIP-LED0805"))
    )
    (comp (ref "LED3")
      (value "Green")
      (footprint "eagle-import:CHIP-LED0805")
      (libsource (lib "eagle-import") (part "LEDCHIP-LED0805"))
    )
    (comp (ref "LED4")
      (value "Green")
      (footprint "eagle-import:CHIP-LED0805")
      (libsource (lib "eagle-import") (part "LEDCHIP-LED0805"))
    )
    (comp (ref "R1")
      (value "0R")
      (footprint "eagle-import:R0805")
      (libsource (lib "eagle-import") (part "R-US_R0805"))
    )
    (comp (ref "R2")
      (value "470R")
      (footprint "eagle-import:R0805")
      (libsource (lib "eagle-import") (part "R-US_R0805"))
    )
    (comp (ref "R3")
      (value "0R")
      (footprint "eagle-import:R0805")
      (libsource (lib "eagle-import") (part "R-US_R0805"))
    )
    (comp (ref "R4")
      (value "270R")
      (footprint "eagle-import:R0805")
      (libsource (lib "eagle-import") (part "R-US_R0805"))
    )
    (comp (ref "R5")
      (value "0R")
      (footprint "eagle-import:R0805")
      (libsource (lib "eagle-import") (part "R-US_R0805"))
    )
    (comp (ref "R6")
      (value "1K")
      (footprint "eagle-import:R0805")
      (libsource (lib "eagle-import") (part "R-US_R0805"))
    )
    (comp (ref "R7")
      (value "2K7")
      (footprint "eagle-import:R0805")
      (libsource (lib "eagle-import") (part "R-US_R0805"))
    )
    (comp (ref "X1")
      (value "W237-02P")
      (footprint "eagle-import:W237-132")
      (libsource (lib "eagle-import") (part "W237-02P"))
    )
    (comp (ref "X2")
      (value "W237-02P")
      (footprint "eagle-import:W237-132")
      (libsource (lib "eagle-import") (part "W237-02P"))
    )
    (comp (ref "X3")
      (value "W237-02P")
      (footprint "eagle-import:W237-132")
      (libsource (lib "eagle-import") (part "W237-02P"))
    )
    (comp (ref "C9")
      (value "10uF/6V/lowESR")
      (footprint "eagle-import:SMC_A")
      (libsource (lib "eagle-import") (part "CPOL-USSMCA"))
    )
    (comp (ref "C10")
      (value "100nF")
      (footprint "eagle-import:C0603")
      (libsource (lib "eagle-import") (part "C-EUC0603"))
    )
    (comp (ref "C11")
      (value "100nF")
      (footprint "eagle-import:C0603")
      (libsource (lib "eagle-import") (part "C-EUC0603"))
    )
    (comp (ref "C12")
      (value "100nF")
      (footprint "eagle-import:C0603")
      (libsource (lib "eagle-import") (part "C-EUC0603"))
    )
    (comp (ref "C13")
      (value "22pF")
      (footprint "eagle-import:C0805")
      (libsource (lib "eagle-import") (part "C-EUC0805"))
    )
    (comp (ref "C14")
      (value "22pF")
      (footprint "eagle-import:C0805")
      (libsource (lib "eagle-import") (part "C-EUC0805"))
    )
    (comp (ref "CN1")
      (value "HDR-1X5-SIP-100")
      (footprint "eagle-import:SIP-100-5V")
      (libsource (lib "eagle-import") (part "HDR-1X5-SIP-100"))
    )
    (comp (ref "IC2")
      (value "DSPIC33FJ128MC804-I/PT")
      (footprint "eagle-import:TQFP44")
      (libsource (lib "eagle-import") (part "DSPIC33FJXXMC804SMD"))
    )
    (comp (ref "LED5")
      (value "Green")
      (footprint "eagle-import:CHIP-LED0805")
      (libsource (lib "eagle-import") (part "LEDCHIP-LED0805"))
    )
    (comp (ref "Q1")
      (value "10MHz")
      (footprint "eagle-import:HC49UP")
      (libsource (lib "eagle-import") (part "CRYSTALHC49UP"))
    )
    (comp (ref "R8")
      (value "1K")
      (footprint "eagle-import:R0805")
      (libsource (lib "eagle-import") (part "R-US_R0805"))
    )
    (comp (ref "R9")
      (value "1K")
      (footprint "eagle-import:R0805")
      (libsource (lib "eagle-import") (part "R-US_R0805"))
    )
    (comp (ref "R10")
      (value "10K")
      (footprint "eagle-import:R0805")
      (libsource (lib "eagle-import") (part "R-US_R0805"))
    )
    (comp (ref "R11")
      (value "10K")
      (footprint "eagle-import:R0805")
      (libsource (lib "eagle-import") (part "R-US_R0805"))
    )
    (comp (ref "R12")
      (value "10K")
      (footprint "eagle-import:R0805")
      (libsource (lib "eagle-import") (part "R-US_R0805"))
    )
    (comp (ref "R13")
      (value "270R")
      (footprint "eagle-import:R0805")
      (libsource (lib "eagle-import") (part "R-US_R0805"))
    )
    (comp (ref "S1")
      (value "10-XX")
      (footprint "eagle-import:B3F-10XX")
      (libsource (lib "eagle-import") (part "10-XX"))
    )
  )
  (nets
    (net (code "1") (name "+3V3") (class "Default")
      (node (ref "C10") (pin "1") (pinfunction "1_1") (pintype "passive"))
      (node (ref "C11") (pin "1") (pinfunction "1_1") (pintype "passive"))
      (node (ref "C12") (pin "1") (pinfunction "1_1") (pintype "passive"))
      (node (ref "C3") (pin "+") (pinfunction "+_+") (pintype "passive"))
      (node (ref "C32") (pin "2") (pinfunction "2_2") (pintype "passive"))
      (node (ref "C34") (pin "2") (pinfunction "2_2") (pintype "passive"))
      (node (ref "C4") (pin "1") (pinfunction "1_1") (pintype "passive"))
      (node (ref "CN1") (pin "2") (pinfunction "2_2") (pintype "passive"))
      (node (ref "IC1") (pin "2") (pinfunction "OUT_2") (pintype "passive"))
      (node (ref "IC2") (pin "17") (pinfunction "AVDD_17") (pintype "passive"))
      (node (ref "IC2") (pin "28") (pinfunction "VDD_28") (pintype "passive"))
      (node (ref "IC2") (pin "40") (pinfunction "VDD_40") (pintype "passive"))
      (node (ref "IC7") (pin "16") (pinfunction "VDD_16") (pintype "passive"))
      (node (ref "IC7") (pin "2") (pinfunction "VDD_2") (pintype "passive"))
      (node (ref "IC8") (pin "16") (pinfunction "VCC_16") (pintype "power_in"))
      (node (ref "LED2") (pin "A") (pinfunction "A_A") (pintype "passive"))
      (node (ref "LED5") (pin "A") (pinfunction "A_A") (pintype "passive"))
      (node (ref "R12") (pin "2") (pinfunction "2_2") (pintype "passive"))
      (node (ref "SV1") (pin "2") (pinfunction "2_2") (pintype "passive"))
    )
    (net (code "2") (name "+5V") (class "Default")
      (node (ref "C1") (pin "+") (pinfunction "+_+") (pintype "passive"))
      (node (ref "C2") (pin "1") (pinfunction "1_1") (pintype "passive"))
      (node (ref "C35") (pin "1") (pinfunction "1_1") (pintype "passive"))
      (node (ref "F1") (pin "2") (pinfunction "2_2") (pintype "passive"))
      (node (ref "IC1") (pin "3") (pinfunction "IN_3") (pintype "input"))
      (node (ref "IC3") (pin "5") (pinfunction "VCC_5") (pintype "power_in"))
      (node (ref "IC9") (pin "20") (pinfunction "VDD_20") (pintype "power_in"))
      (node (ref "J10") (pin "2") (pinfunction "S_2") (pintype "passive"))
      (node (ref "J11") (pin "2") (pinfunction "S_2") (pintype "passive"))
      (node (ref "J9") (pin "2") (pinfunction "S_2") (pintype "passive"))
      (node (ref "LED1") (pin "A") (pinfunction "A_A") (pintype "passive"))
      (node (ref "R14") (pin "2") (pinfunction "2_2") (pintype "passive"))
      (node (ref "R40") (pin "2") (pinfunction "2_2") (pintype "passive"))
      (node (ref "R8") (pin "2") (pinfunction "2_2") (pintype "passive"))
      (node (ref "R9") (pin "2") (pinfunction "2_2") (pintype "passive"))
      (node (ref "SJ1") (pin "3") (pinfunction "3_3") (pintype "passive"))
      (node (ref "SJ10") (pin "3") (pinfunction "3_3") (pintype "passive"))
      (node (ref "SJ11") (pin "3") (pinfunction "3_3") (pintype "passive"))
      (node (ref "SJ12") (pin "3") (pinfunction "3_3") (pintype "passive"))
      (node (ref "SJ13") (pin "3") (pinfunction "3_3") (pintype "passive"))
      (node (ref "SJ14") (pin "3") (pinfunction "3_3") (pintype "passive"))
      (node (ref "SJ15") (pin "3") (pinfunction "3_3") (pintype "passive"))
      (node (ref "SJ16") (pin "3") (pinfunction "3_3") (pintype "passive"))
      (node (ref "SJ17") (pin "3") (pinfunction "3_3") (pintype "passive"))
      (node (ref "SJ18") (pin "3") (pinfunction "3_3") (pintype "passive"))
      (node (ref "SJ19") (pin "3") (pinfunction "3_3") (pintype "passive"))
      (node (ref "SJ2") (pin "3") (pinfunction "3_3") (pintype "passive"))
      (node (ref "SJ3") (pin "3") (pinfunction "3_3") (pintype "passive"))
      (node (ref "SJ4") (pin "3") (pinfunction "3_3") (pintype "passive"))
      (node (ref "SJ5") (pin "3") (pinfunction "3_3") (pintype "passive"))
      (node (ref "SJ6") (pin "3") (pinfunction "3_3") (pintype "passive"))
      (node (ref "SJ7") (pin "3") (pinfunction "3_3") (pintype "passive"))
      (node (ref "SJ8") (pin "3") (pinfunction "3_3") (pintype "passive"))
      (node (ref "SJ9") (pin "3") (pinfunction "3_3") (pintype "passive"))
    )
    (net (code "3") (name "+12V") (class "Default")
      (node (ref "F2") (pin "2") (pinfunction "2_2") (pintype "passive"))
      (node (ref "J26") (pin "2") (pinfunction "S_2") (pintype "passive"))
      (node (ref "J27") (pin "2") (pinfunction "S_2") (pintype "passive"))
      (node (ref "J28") (pin "2") (pinfunction "S_2") (pintype "passive"))
      (node (ref "J29") (pin "2") (pinfunction "S_2") (pintype "passive"))
      (node (ref "J30") (pin "2") (pinfunction "S_2") (pintype "passive"))
      (node (ref "J31") (pin "2") (pinfunction "S_2") (pintype "passive"))
      (node (ref "J32") (pin "2") (pinfunction "S_2") (pintype "passive"))
      (node (ref "J33") (pin "2") (pinfunction "S_2") (pintype "passive"))
      (node (ref "J34") (pin "2") (pinfunction "S_2") (pintype "passive"))
      (node (ref "J35") (pin "2") (pinfunction "S_2") (pintype "passive"))
      (node (ref "J36") (pin "2") (pinfunction "S_2") (pintype "passive"))
      (node (ref "J37") (pin "2") (pinfunction "S_2") (pintype "passive"))
      (node (ref "J38") (pin "2") (pinfunction "S_2") (pintype "passive"))
      (node (ref "J39") (pin "2") (pinfunction "S_2") (pintype "passive"))
      (node (ref "J40") (pin "2") (pinfunction "S_2") (pintype "passive"))
      (node (ref "J41") (pin "2") (pinfunction "S_2") (pintype "passive"))
      (node (ref "J6") (pin "2") (pinfunction "S_2") (pintype "passive"))
      (node (ref "J7") (pin "2") (pinfunction "S_2") (pintype "passive"))
      (node (ref "J8") (pin "2") (pinfunction "S_2") (pintype "passive"))
      (node (ref "LED3") (pin "A") (pinfunction "A_A") (pintype "passive"))
    )
    (net (code "4") (name "+24V") (class "Default")
      (node (ref "C15") (pin "+") (pinfunction "+_+") (pintype "passive"))
      (node (ref "C20") (pin "+") (pinfunction "+_+") (pintype "passive"))
      (node (ref "C25") (pin "+") (pinfunction "+_+") (pintype "passive"))
      (node (ref "C7") (pin "+") (pinfunction "+_+") (pintype "passive"))
      (node (ref "C8") (pin "1") (pinfunction "1_1") (pintype "passive"))
      (node (ref "IC4") (pin "2") (pinfunction "VS_2") (pintype "power_in"))
      (node (ref "IC5") (pin "2") (pinfunction "VS_2") (pintype "power_in"))
      (node (ref "IC6") (pin "2") (pinfunction "VS_2") (pintype "power_in"))
      (node (ref "LED4") (pin "A") (pinfunction "A_A") (pintype "passive"))
      (node (ref "X3") (pin "2") (pinfunction "KL_2") (pintype "passive"))
    )
    (net (code "5") (name "0V") (class "Default")
      (node (ref "C15") (pin "-") (pinfunction "-_-") (pintype "passive"))
      (node (ref "C16") (pin "2") (pinfunction "2_2") (pintype "passive"))
      (node (ref "C20") (pin "-") (pinfunction "-_-") (pintype "passive"))
      (node (ref "C21") (pin "2") (pinfunction "2_2") (pintype "passive"))
      (node (ref "C25") (pin "-") (pinfunction "-_-") (pintype "passive"))
      (node (ref "C26") (pin "2") (pinfunction "2_2") (pintype "passive"))
      (node (ref "C7") (pin "-") (pinfunction "-_-") (pintype "passive"))
      (node (ref "C8") (pin "2") (pinfunction "2_2") (pintype "passive"))
      (node (ref "D1") (pin "A") (pinfunction "A_A") (pintype "passive"))
      (node (ref "D2") (pin "A") (pinfunction "A_A") (pintype "passive"))
      (node (ref "D3") (pin "A") (pinfunction "A_A") (pintype "passive"))
      (node (ref "D4") (pin "A") (pinfunction "A_A") (pintype "passive"))
      (node (ref "D5") (pin "A") (pinfunction "A_A") (pintype "passive"))
      (node (ref "D6") (pin "A") (pinfunction "A_A") (pintype "passive"))
      (node (ref "IC4") (pin "10") (pinfunction "SENSE_10") (pintype "input"))
      (node (ref "IC5") (pin "10") (pinfunction "SENSE_10") (pintype "input"))
      (node (ref "IC6") (pin "10") (pinfunction "SENSE_10") (pintype "input"))
      (node (ref "R18") (pin "1") (pinfunction "1_1") (pintype "passive"))
      (node (ref "R20") (pin "1") (pinfunction "1_1") (pintype "passive"))
      (node (ref "R22") (pin "1") (pinfunction "1_1") (pintype "passive"))
      (node (ref "R7") (pin "1") (pinfunction "1_1") (pintype "passive"))
      (node (ref "X3") (pin "1") (pinfunction "KL_1") (pintype "passive"))
    )
    (net (code "6") (name "BT_RST") (class "Default")
      (node (ref "IC2") (pin "35") (pinfunction "TDI/PMA9/RA9_35") (pintype "passive"))
      (node (ref "IC7") (pin "17") (pinfunction "RES_17") (pintype "passive"))
    )
    (net (code "7") (name "ENC_1_CHA") (class "Default")
      (node (ref "IC2") (pin "38") (pinfunction "RP21*/CN26/PMA3/RC5_38") (pintype "passive"))
      (node (ref "J9") (pin "3") (pinfunction "S_3") (pintype "passive"))
    )
    (net (code "8") (name "ENC_1_CHB") (class "Default")
      (node (ref "IC2") (pin "37") (pinfunction "RP20*/CN25/PMA4/RC4_37") (pintype "passive"))
      (node (ref "J9") (pin "4") (pinfunction "S_4") (pintype "passive"))
    )
    (net (code "9") (name "ENC_2_CHA") (class "Default")
      (node (ref "IC2") (pin "36") (pinfunction "RP19*/CN28/PMBE/RC3_36") (pintype "passive"))
      (node (ref "J10") (pin "3") (pinfunction "S_3") (pintype "passive"))
    )
    (net (code "10") (name "ENC_2_CHB") (class "Default")
      (node (ref "IC2") (pin "33") (pinfunction "SOSCI/RP4*/CN1/RB4_33") (pintype "passive"))
      (node (ref "J10") (pin "4") (pinfunction "S_4") (pintype "passive"))
    )
    (net (code "11") (name "ENC_3") (class "Default")
      (node (ref "IC2") (pin "9") (pinfunction "PGEC2/PWM1L3/RP11*/CN15/PMD1/RB11_9") (pintype "passive"))
      (node (ref "IC3") (pin "4") (pinfunction "O_4") (pintype "output"))
    )
    (net (code "12") (name "FROM_TX_RS232_M") (class "Default")
      (node (ref "IC8") (pin "13") (pinfunction "R1IN_13") (pintype "input"))
      (node (ref "J12") (pin "2") (pinfunction "S_2") (pintype "passive"))
    )
    (net (code "13") (name "GND") (class "Default")
      (node (ref "C10") (pin "2") (pinfunction "2_2") (pintype "passive"))
      (node (ref "C11") (pin "2") (pinfunction "2_2") (pintype "passive"))
      (node (ref "C12") (pin "2") (pinfunction "2_2") (pintype "passive"))
      (node (ref "C13") (pin "2") (pinfunction "2_2") (pintype "passive"))
      (node (ref "C14") (pin "2") (pinfunction "2_2") (pintype "passive"))
      (node (ref "C3") (pin "-") (pinfunction "-_-") (pintype "passive"))
      (node (ref "C33") (pin "1") (pinfunction "1_1") (pintype "passive"))
      (node (ref "C34") (pin "1") (pinfunction "1_1") (pintype "passive"))
      (node (ref "C35") (pin "2") (pinfunction "2_2") (pintype "passive"))
      (node (ref "C36") (pin "2") (pinfunction "2_2") (pintype "passive"))
      (node (ref "C4") (pin "2") (pinfunction "2_2") (pintype "passive"))
      (node (ref "C9") (pin "-") (pinfunction "-_-") (pintype "passive"))
      (node (ref "CN1") (pin "3") (pinfunction "3_3") (pintype "passive"))
      (node (ref "IC1") (pin "1") (pinfunction "ADJ_1") (pintype "input"))
      (node (ref "IC2") (pin "16") (pinfunction "AVSS_16") (pintype "passive"))
      (node (ref "IC2") (pin "29") (pinfunction "VSS_29") (pintype "passive"))
      (node (ref "IC2") (pin "39") (pinfunction "VSS_39") (pintype "passive"))
      (node (ref "IC2") (pin "6") (pinfunction "VSS_6") (pintype "passive"))
      (node (ref "IC4") (pin "6") (pinfunction "GND_6") (pintype "power_in"))
      (node (ref "IC5") (pin "6") (pinfunction "GND_6") (pintype "power_in"))
      (node (ref "IC6") (pin "6") (pinfunction "GND_6") (pintype "power_in"))
      (node (ref "IC7") (pin "1") (pinfunction "GND_1") (pintype "passive"))
      (node (ref "IC7") (pin "14") (pinfunction "GND_14") (pintype "passive"))
      (node (ref "IC7") (pin "15") (pinfunction "GND_15") (pintype "passive"))
      (node (ref "IC7") (pin "28") (pinfunction "GND_28") (pintype "passive"))
      (node (ref "IC8") (pin "10") (pinfunction "T2IN_10") (pintype "input"))
      (node (ref "IC8") (pin "15") (pinfunction "GND_15") (pintype "power_in"))
      (node (ref "IC8") (pin "8") (pinfunction "R2IN_8") (pintype "input"))
      (node (ref "IC9") (pin "1") (pinfunction "VSS_1") (pintype "power_in"))
      (node (ref "IC9") (pin "16") (pinfunction "A0_16") (pintype "bidirectional"))
      (node (ref "IC9") (pin "17") (pinfunction "A1_17") (pintype "bidirectional"))
      (node (ref "IC9") (pin "18") (pinfunction "A2_18") (pintype "bidirectional"))
      (node (ref "IC9") (pin "19") (pinfunction "VSS2_19") (pintype "power_in"))
      (node (ref "IC9") (pin "8") (pinfunction "VSS1_8") (pintype "power_in"))
      (node (ref "J12") (pin "1") (pinfunction "S_1") (pintype "passive"))
      (node (ref "J13") (pin "3") (pinfunction "S_3") (pintype "passive"))
      (node (ref "R10") (pin "1") (pinfunction "1_1") (pintype "passive"))
      (node (ref "R11") (pin "2") (pinfunction "2_2") (pintype "passive"))
      (node (ref "R18") (pin "2") (pinfunction "2_2") (pintype "passive"))
      (node (ref "R20") (pin "2") (pinfunction "2_2") (pintype "passive"))
      (node (ref "R22") (pin "2") (pinfunction "2_2") (pintype "passive"))
      (node (ref "R3") (pin "1") (pinfunction "1_1") (pintype "passive"))
      (node (ref "R4") (pin "1") (pinfunction "1_1") (pintype "passive"))
      (node (ref "S1") (pin "3") (pinfunction "P_3") (pintype "passive"))
      (node (ref "S1") (pin "4") (pinfunction "P1_4") (pintype "passive"))
      (node (ref "SV1") (pin "1") (pinfunction "1_1") (pintype "passive"))
      (node (ref "SV1") (pin "4") (pinfunction "4_4") (pintype "passive"))
    )
    (net (code "14") (name "GNDIO") (class "Default")
      (node (ref "C1") (pin "-") (pinfunction "-_-") (pintype "passive"))
      (node (ref "C2") (pin "2") (pinfunction "2_2") (pintype "passive"))
      (node (ref "C5") (pin "-") (pinfunction "-_-") (pintype "passive"))
      (node (ref "C6") (pin "2") (pinfunction "2_2") (pintype "passive"))
      (node (ref "IC3") (pin "3") (pinfunction "GND_3") (pintype "power_in"))
      (node (ref "J10") (pin "1") (pinfunction "S_1") (pintype "passive"))
      (node (ref "J11") (pin "1") (pinfunction "S_1") (pintype "passive"))
      (node (ref "J26") (pin "1") (pinfunction "S_1") (pintype "passive"))
      (node (ref "J27") (pin "1") (pinfunction "S_1") (pintype "passive"))
      (node (ref "J28") (pin "1") (pinfunction "S_1") (pintype "passive"))
      (node (ref "J29") (pin "1") (pinfunction "S_1") (pintype "passive"))
      (node (ref "J30") (pin "1") (pinfunction "S_1") (pintype "passive"))
      (node (ref "J31") (pin "1") (pinfunction "S_1") (pintype "passive"))
      (node (ref "J32") (pin "1") (pinfunction "S_1") (pintype "passive"))
      (node (ref "J33") (pin "1") (pinfunction "S_1") (pintype "passive"))
      (node (ref "J34") (pin "1") (pinfunction "S_1") (pintype "passive"))
      (node (ref "J35") (pin "1") (pinfunction "S_1") (pintype "passive"))
      (node (ref "J36") (pin "1") (pinfunction "S_1") (pintype "passive"))
      (node (ref "J37") (pin "1") (pinfunction "S_1") (pintype "passive"))
      (node (ref "J38") (pin "1") (pinfunction "S_1") (pintype "passive"))
      (node (ref "J39") (pin "1") (pinfunction "S_1") (pintype "passive"))
      (node (ref "J40") (pin "1") (pinfunction "S_1") (pintype "passive"))
      (node (ref "J41") (pin "1") (pinfunction "S_1") (pintype "passive"))
      (node (ref "J6") (pin "1") (pinfunction "S_1") (pintype "passive"))
      (node (ref "J7") (pin "1") (pinfunction "S_1") (pintype "passive"))
      (node (ref "J8") (pin "1") (pinfunction "S_1") (pintype "passive"))
      (node (ref "J9") (pin "1") (pinfunction "S_1") (pintype "passive"))
      (node (ref "R1") (pin "1") (pinfunction "1_1") (pintype "passive"))
      (node (ref "R2") (pin "1") (pinfunction "1_1") (pintype "passive"))
      (node (ref "R3") (pin "2") (pinfunction "2_2") (pintype "passive"))
      (node (ref "R5") (pin "1") (pinfunction "1_1") (pintype "passive"))
      (node (ref "R6") (pin "1") (pinfunction "1_1") (pintype "passive"))
      (node (ref "SJ1") (pin "1") (pinfunction "1_1") (pintype "passive"))
      (node (ref "SJ10") (pin "1") (pinfunction "1_1") (pintype "passive"))
      (node (ref "SJ11") (pin "1") (pinfunction "1_1") (pintype "passive"))
      (node (ref "SJ12") (pin "1") (pinfunction "1_1") (pintype "passive"))
      (node (ref "SJ13") (pin "1") (pinfunction "1_1") (pintype "passive"))
      (node (ref "SJ14") (pin "1") (pinfunction "1_1") (pintype "passive"))
      (node (ref "SJ15") (pin "1") (pinfunction "1_1") (pintype "passive"))
      (node (ref "SJ16") (pin "1") (pinfunction "1_1") (pintype "passive"))
      (node (ref "SJ17") (pin "1") (pinfunction "1_1") (pintype "passive"))
      (node (ref "SJ18") (pin "1") (pinfunction "1_1") (pintype "passive"))
      (node (ref "SJ19") (pin "1") (pinfunction "1_1") (pintype "passive"))
      (node (ref "SJ2") (pin "1") (pinfunction "1_1") (pintype "passive"))
      (node (ref "SJ3") (pin "1") (pinfunction "1_1") (pintype "passive"))
      (node (ref "SJ4") (pin "1") (pinfunction "1_1") (pintype "passive"))
      (node (ref "SJ5") (pin "1") (pinfunction "1_1") (pintype "passive"))
      (node (ref "SJ6") (pin "1") (pinfunction "1_1") (pintype "passive"))
      (node (ref "SJ7") (pin "1") (pinfunction "1_1") (pintype "passive"))
      (node (ref "SJ8") (pin "1") (pinfunction "1_1") (pintype "passive"))
      (node (ref "SJ9") (pin "1") (pinfunction "1_1") (pintype "passive"))
    )
    (net (code "15") (name "GND_SERVO_5V") (class "Default")
      (node (ref "J1") (pin "1") (pinfunction "S_1") (pintype "passive"))
      (node (ref "J2") (pin "1") (pinfunction "S_1") (pintype "passive"))
      (node (ref "J3") (pin "1") (pinfunction "S_1") (pintype "passive"))
      (node (ref "J4") (pin "1") (pinfunction "S_1") (pintype "passive"))
      (node (ref "R1") (pin "2") (pinfunction "2_2") (pintype "passive"))
      (node (ref "X1") (pin "1") (pinfunction "KL_1") (pintype "passive"))
    )
    (net (code "16") (name "GND_SERVO_12V") (class "Default")
      (node (ref "J5") (pin "1") (pinfunction "S_1") (pintype "passive"))
      (node (ref "R5") (pin "2") (pinfunction "2_2") (pintype "passive"))
      (node (ref "X2") (pin "1") (pinfunction "KL_1") (pintype "passive"))
    )
    (net (code "17") (name "GP0_0") (class "Default")
      (node (ref "IC9") (pin "21") (pinfunction "GP0_0_21") (pintype "bidirectional"))
      (node (ref "R24") (pin "2") (pinfunction "2_2") (pintype "passive"))
      (node (ref "SJ4") (pin "2") (pinfunction "2_2") (pintype "passive"))
    )
    (net (code "18") (name "GP0_1") (class "Default")
      (node (ref "IC9") (pin "22") (pinfunction "GP0_1_22") (pintype "bidirectional"))
      (node (ref "R25") (pin "2") (pinfunction "2_2") (pintype "passive"))
      (node (ref "SJ5") (pin "2") (pinfunction "2_2") (pintype "passive"))
    )
    (net (code "19") (name "GP0_2") (class "Default")
      (node (ref "IC9") (pin "23") (pinfunction "GP0_2_23") (pintype "bidirectional"))
      (node (ref "R26") (pin "2") (pinfunction "2_2") (pintype "passive"))
      (node (ref "SJ6") (pin "2") (pinfunction "2_2") (pintype "passive"))
    )
    (net (code "20") (name "GP0_3") (class "Default")
      (node (ref "IC9") (pin "24") (pinfunction "GP0_3_24") (pintype "bidirectional"))
      (node (ref "R27") (pin "2") (pinfunction "2_2") (pintype "passive"))
      (node (ref "SJ7") (pin "2") (pinfunction "2_2") (pintype "passive"))
    )
    (net (code "21") (name "GP0_4") (class "Default")
      (node (ref "IC9") (pin "25") (pinfunction "GP0_4_25") (pintype "bidirectional"))
      (node (ref "R28") (pin "2") (pinfunction "2_2") (pintype "passive"))
      (node (ref "SJ8") (pin "2") (pinfunction "2_2") (pintype "passive"))
    )
    (net (code "22") (name "GP0_5") (class "Default")
      (node (ref "IC9") (pin "26") (pinfunction "GP0_5_26") (pintype "bidirectional"))
      (node (ref "R29") (pin "2") (pinfunction "2_2") (pintype "passive"))
      (node (ref "SJ9") (pin "2") (pinfunction "2_2") (pintype "passive"))
    )
    (net (code "23") (name "GP0_6") (class "Default")
      (node (ref "IC9") (pin "27") (pinfunction "GP0_6_27") (pintype "bidirectional"))
      (node (ref "R30") (pin "2") (pinfunction "2_2") (pintype "passive"))
      (node (ref "SJ10") (pin "2") (pinfunction "2_2") (pintype "passive"))
    )
    (net (code "24") (name "GP0_7") (class "Default")
      (node (ref "IC9") (pin "28") (pinfunction "GP0_7_28") (pintype "bidirectional"))
      (node (ref "R31") (pin "2") (pinfunction "2_2") (pintype "passive"))
      (node (ref "SJ11") (pin "2") (pinfunction "2_2") (pintype "passive"))
    )
    (net (code "25") (name "GP1_0") (class "Default")
      (node (ref "IC9") (pin "2") (pinfunction "GP1_0_2") (pintype "bidirectional"))
      (node (ref "R32") (pin "2") (pinfunction "2_2") (pintype "passive"))
      (node (ref "SJ12") (pin "2") (pinfunction "2_2") (pintype "passive"))
    )
    (net (code "26") (name "GP1_1") (class "Default")
      (node (ref "IC9") (pin "3") (pinfunction "GP1_1_3") (pintype "bidirectional"))
      (node (ref "R33") (pin "2") (pinfunction "2_2") (pintype "passive"))
      (node (ref "SJ13") (pin "2") (pinfunction "2_2") (pintype "passive"))
    )
    (net (code "27") (name "GP1_2") (class "Default")
      (node (ref "IC9") (pin "4") (pinfunction "GP1_2_4") (pintype "bidirectional"))
      (node (ref "R34") (pin "2") (pinfunction "2_2") (pintype "passive"))
      (node (ref "SJ14") (pin "2") (pinfunction "2_2") (pintype "passive"))
    )
    (net (code "28") (name "GP1_3") (class "Default")
      (node (ref "IC9") (pin "5") (pinfunction "GP1_3_5") (pintype "bidirectional"))
      (node (ref "R35") (pin "2") (pinfunction "2_2") (pintype "passive"))
      (node (ref "SJ15") (pin "2") (pinfunction "2_2") (pintype "passive"))
    )
    (net (code "29") (name "GP1_4") (class "Default")
      (node (ref "IC9") (pin "7") (pinfunction "GP1_4_7") (pintype "bidirectional"))
      (node (ref "R36") (pin "2") (pinfunction "2_2") (pintype "passive"))
      (node (ref "SJ16") (pin "2") (pinfunction "2_2") (pintype "passive"))
    )
    (net (code "30") (name "GP1_5") (class "Default")
      (node (ref "IC9") (pin "11") (pinfunction "GP1_5_11") (pintype "bidirectional"))
      (node (ref "R37") (pin "2") (pinfunction "2_2") (pintype "passive"))
      (node (ref "SJ17") (pin "2") (pinfunction "2_2") (pintype "passive"))
    )
    (net (code "31") (name "GP1_6") (class "Default")
      (node (ref "IC9") (pin "12") (pinfunction "GP1_6_12") (pintype "bidirectional"))
      (node (ref "R38") (pin "2") (pinfunction "2_2") (pintype "passive"))
      (node (ref "SJ18") (pin "2") (pinfunction "2_2") (pintype "passive"))
    )
    (net (code "32") (name "GP1_7") (class "Default")
      (node (ref "IC9") (pin "13") (pinfunction "GP1_7_13") (pintype "bidirectional"))
      (node (ref "R39") (pin "2") (pinfunction "2_2") (pintype "passive"))
      (node (ref "SJ19") (pin "2") (pinfunction "2_2") (pintype "passive"))
    )
    (net (code "33") (name "I2C_SCL_(5V)") (class "Default")
      (node (ref "IC2") (pin "42") (pinfunction "PGEC3/ASCL1/RP6*/CN24/PMD6/RB6_42") (pintype "passive"))
      (node (ref "IC9") (pin "14") (pinfunction "SCL_14") (pintype "bidirectional"))
      (node (ref "J13") (pin "2") (pinfunction "S_2") (pintype "passive"))
      (node (ref "R8") (pin "1") (pinfunction "1_1") (pintype "passive"))
    )
    (net (code "34") (name "I2C_SDA_(5V)") (class "Default")
      (node (ref "IC2") (pin "41") (pinfunction "PGED3/ASDA1/RP5*/CN27/PMD7/RB5_41") (pintype "passive"))
      (node (ref "IC9") (pin "15") (pinfunction "SDA_15") (pintype "bidirectional"))
      (node (ref "J13") (pin "1") (pinfunction "S_1") (pintype "passive"))
      (node (ref "R9") (pin "1") (pinfunction "1_1") (pintype "passive"))
    )
    (net (code "35") (name "MISO") (class "Default")
      (node (ref "IC2") (pin "3") (pinfunction "PWM2L1/RP23*/CN17/PMA0/RC7_3") (pintype "passive"))
      (node (ref "SV1") (pin "7") (pinfunction "7_7") (pintype "passive"))
    )
    (net (code "36") (name "MOSI") (class "Default")
      (node (ref "IC2") (pin "2") (pinfunction "PWM2H1/RP22*/CN18/PMA1/RC6_2") (pintype "passive"))
      (node (ref "SV1") (pin "6") (pinfunction "6_6") (pintype "passive"))
    )
    (net (code "37") (name "MOT_1_PWM") (class "Default")
      (node (ref "IC2") (pin "14") (pinfunction "PWM1H1/DAC1LP/RTCC/RP14*/CN12/PMWR/RB14_14") (pintype "passive"))
      (node (ref "IC4") (pin "11") (pinfunction "ENABLE_11") (pintype "input"))
    )
    (net (code "38") (name "MOT_1_SIGN1") (class "Default")
      (node (ref "IC2") (pin "19") (pinfunction "AN0/VREF+/CN2/RA0_19") (pintype "passive"))
      (node (ref "IC4") (pin "5") (pinfunction "IN1_5") (pintype "input"))
    )
    (net (code "39") (name "MOT_1_SIGN2") (class "Default")
      (node (ref "IC2") (pin "20") (pinfunction "AN1/VREF-/CN3/RA1_20") (pintype "passive"))
      (node (ref "IC4") (pin "7") (pinfunction "IN2_7") (pintype "input"))
    )
    (net (code "40") (name "MOT_2_PWM") (class "Default")
      (node (ref "IC2") (pin "10") (pinfunction "PWM1H2/DAC1RP/RP12*/CN14/PMD0/RB12_10") (pintype "passive"))
      (node (ref "IC5") (pin "11") (pinfunction "ENABLE_11") (pintype "input"))
    )
    (net (code "41") (name "MOT_2_SIGN1") (class "Default")
      (node (ref "IC2") (pin "13") (pinfunction "TCK/PMA7/RA7_13") (pintype "passive"))
      (node (ref "IC5") (pin "5") (pinfunction "IN1_5") (pintype "input"))
    )
    (net (code "42") (name "MOT_2_SIGN2") (class "Default")
      (node (ref "IC2") (pin "15") (pinfunction "PWM1L1/DAC1LN/RP15*/CN11/PMCS1/RB15_15") (pintype "passive"))
      (node (ref "IC5") (pin "7") (pinfunction "IN2_7") (pintype "input"))
    )
    (net (code "43") (name "MOT_3_PWM") (class "Default")
      (node (ref "IC2") (pin "8") (pinfunction "PGED2/EMCD2/PWM1H3/RP10*/CN16/PMD2/RB10_8") (pintype "passive"))
      (node (ref "IC6") (pin "11") (pinfunction "ENABLE_11") (pintype "input"))
    )
    (net (code "44") (name "MOT_3_SIGN1") (class "Default")
      (node (ref "IC2") (pin "11") (pinfunction "PWM1L2/DAC1RN/RP13*/CN13/PMRD/RB13_11") (pintype "passive"))
      (node (ref "IC6") (pin "5") (pinfunction "IN1_5") (pintype "input"))
    )
    (net (code "45") (name "MOT_3_SIGN2") (class "Default")
      (node (ref "IC2") (pin "12") (pinfunction "TMS/PMA10/RA10_12") (pintype "passive"))
      (node (ref "IC6") (pin "7") (pinfunction "IN2_7") (pintype "input"))
    )
    (net (code "46") (name "Net-(C19-Pad2)") (class "Default")
      (node (ref "C19") (pin "2") (pinfunction "2_2") (pintype "passive"))
      (node (ref "R19") (pin "1") (pinfunction "1_1") (pintype "passive"))
    )
    (net (code "47") (name "Net-(C24-Pad2)") (class "Default")
      (node (ref "C24") (pin "2") (pinfunction "2_2") (pintype "passive"))
      (node (ref "R21") (pin "1") (pinfunction "1_1") (pintype "passive"))
    )
    (net (code "48") (name "Net-(C29-Pad2)") (class "Default")
      (node (ref "C29") (pin "2") (pinfunction "2_2") (pintype "passive"))
      (node (ref "R23") (pin "1") (pinfunction "1_1") (pintype "passive"))
    )
    (net (code "49") (name "Net-(IC2-OSC1{slash}CLKI{slash}CN30{slash}RA2)") (class "Default")
      (node (ref "C13") (pin "1") (pinfunction "1_1") (pintype "passive"))
      (node (ref "IC2") (pin "30") (pinfunction "OSC1/CLKI/CN30/RA2_30") (pintype "passive"))
      (node (ref "Q1") (pin "1") (pinfunction "1_1") (pintype "passive"))
    )
    (net (code "50") (name "Net-(IC2-OSC2{slash}CLKO{slash}CN29{slash}RA3)") (class "Default")
      (node (ref "C14") (pin "1") (pinfunction "1_1") (pintype "passive"))
      (node (ref "IC2") (pin "31") (pinfunction "OSC2/CLKO/CN29/RA3_31") (pintype "passive"))
      (node (ref "Q1") (pin "2") (pinfunction "2_2") (pintype "passive"))
    )
    (net (code "51") (name "Net-(IC2-VCAP{slash}VDDCORE)") (class "Default")
      (node (ref "C9") (pin "+") (pinfunction "+_+") (pintype "passive"))
      (node (ref "IC2") (pin "7") (pinfunction "VCAP/VDDCORE_7") (pintype "passive"))
    )
    (net (code "52") (name "Net-(IC3-I0)") (class "Default")
      (node (ref "IC3") (pin "1") (pinfunction "I0_1") (pintype "input"))
      (node (ref "J11") (pin "3") (pinfunction "S_3") (pintype "passive"))
    )
    (net (code "53") (name "Net-(IC3-I1)") (class "Default")
      (node (ref "IC3") (pin "2") (pinfunction "I1_2") (pintype "input"))
      (node (ref "J11") (pin "4") (pinfunction "S_4") (pintype "passive"))
    )
    (net (code "54") (name "Net-(IC4-CBOOT1)") (class "Default")
      (node (ref "C17") (pin "1") (pinfunction "1_1") (pintype "passive"))
      (node (ref "IC4") (pin "4") (pinfunction "CBOOT1_4") (pintype "input"))
    )
    (net (code "55") (name "Net-(IC4-CBOOT2)") (class "Default")
      (node (ref "C18") (pin "1") (pinfunction "1_1") (pintype "passive"))
      (node (ref "IC4") (pin "8") (pinfunction "CBOOT2_8") (pintype "input"))
    )
    (net (code "56") (name "Net-(IC4-OUT1)") (class "Default")
      (node (ref "C17") (pin "2") (pinfunction "2_2") (pintype "passive"))
      (node (ref "D1") (pin "C") (pinfunction "C_C") (pintype "passive"))
      (node (ref "IC4") (pin "3") (pinfunction "OUT1_3") (pintype "output"))
      (node (ref "R19") (pin "2") (pinfunction "2_2") (pintype "passive"))
      (node (ref "X4") (pin "2") (pinfunction "KL_2") (pintype "passive"))
    )
    (net (code "57") (name "Net-(IC4-OUT2)") (class "Default")
      (node (ref "C18") (pin "2") (pinfunction "2_2") (pintype "passive"))
      (node (ref "C19") (pin "1") (pinfunction "1_1") (pintype "passive"))
      (node (ref "D2") (pin "C") (pinfunction "C_C") (pintype "passive"))
      (node (ref "IC4") (pin "1") (pinfunction "OUT2_1") (pintype "output"))
      (node (ref "X4") (pin "1") (pinfunction "KL_1") (pintype "passive"))
    )
    (net (code "58") (name "Net-(IC4-VREF)") (class "Default")
      (node (ref "C16") (pin "1") (pinfunction "1_1") (pintype "passive"))
      (node (ref "IC4") (pin "9") (pinfunction "VREF_9") (pintype "input"))
    )
    (net (code "59") (name "Net-(IC5-CBOOT1)") (class "Default")
      (node (ref "C22") (pin "1") (pinfunction "1_1") (pintype "passive"))
      (node (ref "IC5") (pin "4") (pinfunction "CBOOT1_4") (pintype "input"))
    )
    (net (code "60") (name "Net-(IC5-CBOOT2)") (class "Default")
      (node (ref "C23") (pin "1") (pinfunction "1_1") (pintype "passive"))
      (node (ref "IC5") (pin "8") (pinfunction "CBOOT2_8") (pintype "input"))
    )
    (net (code "61") (name "Net-(IC5-OUT1)") (class "Default")
      (node (ref "C22") (pin "2") (pinfunction "2_2") (pintype "passive"))
      (node (ref "D3") (pin "C") (pinfunction "C_C") (pintype "passive"))
      (node (ref "IC5") (pin "3") (pinfunction "OUT1_3") (pintype "output"))
      (node (ref "R21") (pin "2") (pinfunction "2_2") (pintype "passive"))
      (node (ref "X5") (pin "2") (pinfunction "KL_2") (pintype "passive"))
    )
    (net (code "62") (name "Net-(IC5-OUT2)") (class "Default")
      (node (ref "C23") (pin "2") (pinfunction "2_2") (pintype "passive"))
      (node (ref "C24") (pin "1") (pinfunction "1_1") (pintype "passive"))
      (node (ref "D4") (pin "C") (pinfunction "C_C") (pintype "passive"))
      (node (ref "IC5") (pin "1") (pinfunction "OUT2_1") (pintype "output"))
      (node (ref "X5") (pin "1") (pinfunction "KL_1") (pintype "passive"))
    )
    (net (code "63") (name "Net-(IC5-VREF)") (class "Default")
      (node (ref "C21") (pin "1") (pinfunction "1_1") (pintype "passive"))
      (node (ref "IC5") (pin "9") (pinfunction "VREF_9") (pintype "input"))
    )
    (net (code "64") (name "Net-(IC6-CBOOT1)") (class "Default")
      (node (ref "C27") (pin "1") (pinfunction "1_1") (pintype "passive"))
      (node (ref "IC6") (pin "4") (pinfunction "CBOOT1_4") (pintype "input"))
    )
    (net (code "65") (name "Net-(IC6-CBOOT2)") (class "Default")
      (node (ref "C28") (pin "1") (pinfunction "1_1") (pintype "passive"))
      (node (ref "IC6") (pin "8") (pinfunction "CBOOT2_8") (pintype "input"))
    )
    (net (code "66") (name "Net-(IC6-OUT1)") (class "Default")
      (node (ref "C27") (pin "2") (pinfunction "2_2") (pintype "passive"))
      (node (ref "D5") (pin "C") (pinfunction "C_C") (pintype "passive"))
      (node (ref "IC6") (pin "3") (pinfunction "OUT1_3") (pintype "output"))
      (node (ref "R23") (pin "2") (pinfunction "2_2") (pintype "passive"))
      (node (ref "X6") (pin "2") (pinfunction "KL_2") (pintype "passive"))
    )
    (net (code "67") (name "Net-(IC6-OUT2)") (class "Default")
      (node (ref "C28") (pin "2") (pinfunction "2_2") (pintype "passive"))
      (node (ref "C29") (pin "1") (pinfunction "1_1") (pintype "passive"))
      (node (ref "D6") (pin "C") (pinfunction "C_C") (pintype "passive"))
      (node (ref "IC6") (pin "1") (pinfunction "OUT2_1") (pintype "output"))
      (node (ref "X6") (pin "1") (pinfunction "KL_1") (pintype "passive"))
    )
    (net (code "68") (name "Net-(IC6-VREF)") (class "Default")
      (node (ref "C26") (pin "1") (pinfunction "1_1") (pintype "passive"))
      (node (ref "IC6") (pin "9") (pinfunction "VREF_9") (pintype "input"))
    )
    (net (code "69") (name "Net-(IC7-NCTS)") (class "Default")
      (node (ref "IC7") (pin "10") (pinfunction "NCTS_10") (pintype "passive"))
      (node (ref "IC7") (pin "5") (pinfunction "NRTS_5") (pintype "passive"))
    )
    (net (code "70") (name "Net-(IC8A-C1+)") (class "Default")
      (node (ref "C30") (pin "2") (pinfunction "2_2") (pintype "passive"))
      (node (ref "IC8") (pin "1") (pinfunction "C1+_1") (pintype "bidirectional"))
    )
    (net (code "71") (name "Net-(IC8A-C1-)") (class "Default")
      (node (ref "C30") (pin "1") (pinfunction "1_1") (pintype "passive"))
      (node (ref "IC8") (pin "3") (pinfunction "C1-_3") (pintype "bidirectional"))
    )
    (net (code "72") (name "Net-(IC8A-C2+)") (class "Default")
      (node (ref "C31") (pin "2") (pinfunction "2_2") (pintype "passive"))
      (node (ref "IC8") (pin "4") (pinfunction "C2+_4") (pintype "bidirectional"))
    )
    (net (code "73") (name "Net-(IC8A-C2-)") (class "Default")
      (node (ref "C31") (pin "1") (pinfunction "1_1") (pintype "passive"))
      (node (ref "IC8") (pin "5") (pinfunction "C2-_5") (pintype "bidirectional"))
    )
    (net (code "74") (name "Net-(IC8A-V+)") (class "Default")
      (node (ref "C32") (pin "1") (pinfunction "1_1") (pintype "passive"))
      (node (ref "IC8") (pin "2") (pinfunction "V+_2") (pintype "bidirectional"))
    )
    (net (code "75") (name "Net-(IC8A-V-)") (class "Default")
      (node (ref "C33") (pin "2") (pinfunction "2_2") (pintype "passive"))
      (node (ref "IC8") (pin "6") (pinfunction "V-_6") (pintype "bidirectional"))
    )
    (net (code "76") (name "Net-(IC9-CLK)") (class "Default")
      (node (ref "C36") (pin "1") (pinfunction "1_1") (pintype "passive"))
      (node (ref "IC9") (pin "9") (pinfunction "CLK_9") (pintype "bidirectional"))
      (node (ref "R40") (pin "1") (pinfunction "1_1") (pintype "passive"))
    )
    (net (code "77") (name "Net-(J6C-S)") (class "Default")
      (node (ref "J6") (pin "3") (pinfunction "S_3") (pintype "passive"))
      (node (ref "R15") (pin "1") (pinfunction "1_1") (pintype "passive"))
    )
    (net (code "78") (name "Net-(J7C-S)") (class "Default")
      (node (ref "J7") (pin "3") (pinfunction "S_3") (pintype "passive"))
      (node (ref "R16") (pin "1") (pinfunction "1_1") (pintype "passive"))
    )
    (net (code "79") (name "Net-(J8C-S)") (class "Default")
      (node (ref "J8") (pin "3") (pinfunction "S_3") (pintype "passive"))
      (node (ref "R17") (pin "1") (pinfunction "1_1") (pintype "passive"))
    )
    (net (code "80") (name "Net-(J26C-S)") (class "Default")
      (node (ref "J26") (pin "3") (pinfunction "S_3") (pintype "passive"))
      (node (ref "R24") (pin "1") (pinfunction "1_1") (pintype "passive"))
    )
    (net (code "81") (name "Net-(J27C-S)") (class "Default")
      (node (ref "J27") (pin "3") (pinfunction "S_3") (pintype "passive"))
      (node (ref "R25") (pin "1") (pinfunction "1_1") (pintype "passive"))
    )
    (net (code "82") (name "Net-(J28C-S)") (class "Default")
      (node (ref "J28") (pin "3") (pinfunction "S_3") (pintype "passive"))
      (node (ref "R26") (pin "1") (pinfunction "1_1") (pintype "passive"))
    )
    (net (code "83") (name "Net-(J29C-S)") (class "Default")
      (node (ref "J29") (pin "3") (pinfunction "S_3") (pintype "passive"))
      (node (ref "R27") (pin "1") (pinfunction "1_1") (pintype "passive"))
    )
    (net (code "84") (name "Net-(J30C-S)") (class "Default")
      (node (ref "J30") (pin "3") (pinfunction "S_3") (pintype "passive"))
      (node (ref "R28") (pin "1") (pinfunction "1_1") (pintype "passive"))
    )
    (net (code "85") (name "Net-(J31C-S)") (class "Default")
      (node (ref "J31") (pin "3") (pinfunction "S_3") (pintype "passive"))
      (node (ref "R29") (pin "1") (pinfunction "1_1") (pintype "passive"))
    )
    (net (code "86") (name "Net-(J32C-S)") (class "Default")
      (node (ref "J32") (pin "3") (pinfunction "S_3") (pintype "passive"))
      (node (ref "R30") (pin "1") (pinfunction "1_1") (pintype "passive"))
    )
    (net (code "87") (name "Net-(J33C-S)") (class "Default")
      (node (ref "J33") (pin "3") (pinfunction "S_3") (pintype "passive"))
      (node (ref "R31") (pin "1") (pinfunction "1_1") (pintype "passive"))
    )
    (net (code "88") (name "Net-(J34C-S)") (class "Default")
      (node (ref "J34") (pin "3") (pinfunction "S_3") (pintype "passive"))
      (node (ref "R32") (pin "1") (pinfunction "1_1") (pintype "passive"))
    )
    (net (code "89") (name "Net-(J35C-S)") (class "Default")
      (node (ref "J35") (pin "3") (pinfunction "S_3") (pintype "passive"))
      (node (ref "R33") (pin "1") (pinfunction "1_1") (pintype "passive"))
    )
    (net (code "90") (name "Net-(J36C-S)") (class "Default")
      (node (ref "J36") (pin "3") (pinfunction "S_3") (pintype "passive"))
      (node (ref "R34") (pin "1") (pinfunction "1_1") (pintype "passive"))
    )
    (net (code "91") (name "Net-(J37C-S)") (class "Default")
      (node (ref "J37") (pin "3") (pinfunction "S_3") (pintype "passive"))
      (node (ref "R35") (pin "1") (pinfunction "1_1") (pintype "passive"))
    )
    (net (code "92") (name "Net-(J38C-S)") (class "Default")
      (node (ref "J38") (pin "3") (pinfunction "S_3") (pintype "passive"))
      (node (ref "R36") (pin "1") (pinfunction "1_1") (pintype "passive"))
    )
    (net (code "93") (name "Net-(J39C-S)") (class "Default")
      (node (ref "J39") (pin "3") (pinfunction "S_3") (pintype "passive"))
      (node (ref "R37") (pin "1") (pinfunction "1_1") (pintype "passive"))
    )
    (net (code "94") (name "Net-(J40C-S)") (class "Default")
      (node (ref "J40") (pin "3") (pinfunction "S_3") (pintype "passive"))
      (node (ref "R38") (pin "1") (pinfunction "1_1") (pintype "passive"))
    )
    (net (code "95") (name "Net-(J41C-S)") (class "Default")
      (node (ref "J41") (pin "3") (pinfunction "S_3") (pintype "passive"))
      (node (ref "R39") (pin "1") (pinfunction "1_1") (pintype "passive"))
    )
    (net (code "96") (name "Net-(LED1-PadC)") (class "Default")
      (node (ref "LED1") (pin "C") (pinfunction "C_C") (pintype "passive"))
      (node (ref "R2") (pin "2") (pinfunction "2_2") (pintype "passive"))
    )
    (net (code "97") (name "Net-(LED2-PadC)") (class "Default")
      (node (ref "LED2") (pin "C") (pinfunction "C_C") (pintype "passive"))
      (node (ref "R4") (pin "2") (pinfunction "2_2") (pintype "passive"))
    )
    (net (code "98") (name "Net-(LED3-PadC)") (class "Default")
      (node (ref "LED3") (pin "C") (pinfunction "C_C") (pintype "passive"))
      (node (ref "R6") (pin "2") (pinfunction "2_2") (pintype "passive"))
    )
    (net (code "99") (name "Net-(LED4-PadC)") (class "Default")
      (node (ref "LED4") (pin "C") (pinfunction "C_C") (pintype "passive"))
      (node (ref "R7") (pin "2") (pinfunction "2_2") (pintype "passive"))
    )
    (net (code "100") (name "Net-(LED5-PadC)") (class "Default")
      (node (ref "LED5") (pin "C") (pinfunction "C_C") (pintype "passive"))
      (node (ref "R13") (pin "2") (pinfunction "2_2") (pintype "passive"))
    )
    (net (code "101") (name "PGEC") (class "Default")
      (node (ref "CN1") (pin "5") (pinfunction "5_5") (pintype "passive"))
      (node (ref "IC2") (pin "22") (pinfunction "PGEC1/AN3/C2IN+/RP1*/CN5/RB1_22") (pintype "passive"))
      (node (ref "R11") (pin "1") (pinfunction "1_1") (pintype "passive"))
    )
    (net (code "102") (name "PGED") (class "Default")
      (node (ref "CN1") (pin "4") (pinfunction "4_4") (pintype "passive"))
      (node (ref "IC2") (pin "21") (pinfunction "PGED1/AN2/C2IN-/RP0*/CN4/RB0_21") (pintype "passive"))
      (node (ref "R10") (pin "2") (pinfunction "2_2") (pintype "passive"))
    )
    (net (code "103") (name "RF24_CE") (class "Default")
      (node (ref "IC2") (pin "34") (pinfunction "SOSCO/T1CK/CN0/RA4_34") (pintype "passive"))
      (node (ref "R13") (pin "1") (pinfunction "1_1") (pintype "passive"))
      (node (ref "SV1") (pin "3") (pinfunction "3_3") (pintype "passive"))
    )
    (net (code "104") (name "RST") (class "Default")
      (node (ref "CN1") (pin "1") (pinfunction "1_1") (pintype "passive"))
      (node (ref "IC2") (pin "18") (pinfunction "MCLR_18") (pintype "passive"))
      (node (ref "R12") (pin "1") (pinfunction "1_1") (pintype "passive"))
      (node (ref "S1") (pin "1") (pinfunction "S_1") (pintype "passive"))
      (node (ref "S1") (pin "2") (pinfunction "S1_2") (pintype "passive"))
    )
    (net (code "105") (name "SCK") (class "Default")
      (node (ref "IC2") (pin "4") (pinfunction "RP24*/CN20/PMA5/RC8_4") (pintype "passive"))
      (node (ref "SV1") (pin "5") (pinfunction "5_5") (pintype "passive"))
    )
    (net (code "106") (name "SENSOR_1") (class "Default")
      (node (ref "IC2") (pin "5") (pinfunction "RP25*/CN19/PMA6/RC9_5") (pintype "passive"))
      (node (ref "R15") (pin "2") (pinfunction "2_2") (pintype "passive"))
      (node (ref "SJ1") (pin "2") (pinfunction "2_2") (pintype "passive"))
    )
    (net (code "107") (name "SENSOR_2") (class "Default")
      (node (ref "IC2") (pin "23") (pinfunction "AN4/C1IN-/RP2*/CN6/RB2_23") (pintype "passive"))
      (node (ref "R16") (pin "2") (pinfunction "2_2") (pintype "passive"))
      (node (ref "SJ2") (pin "2") (pinfunction "2_2") (pintype "passive"))
    )
    (net (code "108") (name "SENSOR_3") (class "Default")
      (node (ref "IC2") (pin "32") (pinfunction "TDO/PMA8/RA8_32") (pintype "passive"))
      (node (ref "R17") (pin "2") (pinfunction "2_2") (pintype "passive"))
      (node (ref "SJ3") (pin "2") (pinfunction "2_2") (pintype "passive"))
    )
    (net (code "109") (name "SERVO_1_PWM") (class "Default")
      (node (ref "IC2") (pin "27") (pinfunction "AN8/CVREF/RP18*/PMA2/CN10/RC2_27") (pintype "passive"))
      (node (ref "J1") (pin "3") (pinfunction "S_3") (pintype "passive"))
    )
    (net (code "110") (name "SERVO_2_PWM") (class "Default")
      (node (ref "IC2") (pin "26") (pinfunction "AN7/DAC1LM/RP17*/CN9/RC1_26") (pintype "passive"))
      (node (ref "J2") (pin "3") (pinfunction "S_3") (pintype "passive"))
    )
    (net (code "111") (name "SERVO_3_PWM") (class "Default")
      (node (ref "IC2") (pin "25") (pinfunction "AN6/DAC1RM/RP16*/CN8/RC0_25") (pintype "passive"))
      (node (ref "J3") (pin "3") (pinfunction "S_3") (pintype "passive"))
    )
    (net (code "112") (name "SERVO_4_PWM") (class "Default")
      (node (ref "IC2") (pin "24") (pinfunction "AN5/C1IN+/RP3*/CN7/RB3_24") (pintype "passive"))
      (node (ref "J4") (pin "3") (pinfunction "S_3") (pintype "passive"))
    )
    (net (code "113") (name "SERVO_AX12_UART") (class "Default")
      (node (ref "IC2") (pin "1") (pinfunction "SDA1/RP9*/CN21/PMD3/RB9_1") (pintype "passive"))
      (node (ref "J5") (pin "3") (pinfunction "S_3") (pintype "passive"))
      (node (ref "R14") (pin "1") (pinfunction "1_1") (pintype "passive"))
    )
    (net (code "114") (name "TO_RX_RS232_M") (class "Default")
      (node (ref "IC8") (pin "14") (pinfunction "T1OUT_14") (pintype "output"))
      (node (ref "J12") (pin "3") (pinfunction "S_3") (pintype "passive"))
    )
    (net (code "115") (name "UART_RX") (class "Default")
      (node (ref "IC2") (pin "44") (pinfunction "SCL1/RP8*/CN22/PMD4/RB8_44") (pintype "passive"))
      (node (ref "IC7") (pin "26") (pinfunction "TXD_26") (pintype "passive"))
    )
    (net (code "116") (name "UART_RX_BYPASS") (class "Default")
      (node (ref "IC7") (pin "20") (pinfunction "PIO4_20") (pintype "passive"))
      (node (ref "IC8") (pin "12") (pinfunction "R1OUT_12") (pintype "output"))
    )
    (net (code "117") (name "UART_TX") (class "Default")
      (node (ref "IC2") (pin "43") (pinfunction "INT0/RP7*/CN23/PMD5/RB7_43") (pintype "passive"))
      (node (ref "IC7") (pin "6") (pinfunction "RXD_6") (pintype "passive"))
    )
    (net (code "118") (name "UART_TX_BYPASS") (class "Default")
      (node (ref "IC7") (pin "19") (pinfunction "PIO7_19") (pintype "passive"))
      (node (ref "IC8") (pin "11") (pinfunction "T1IN_11") (pintype "input"))
    )
    (net (code "119") (name "VCC_SERVO_5V") (class "Default")
      (node (ref "F1") (pin "1") (pinfunction "1_1") (pintype "passive"))
      (node (ref "J1") (pin "2") (pinfunction "S_2") (pintype "passive"))
      (node (ref "J2") (pin "2") (pinfunction "S_2") (pintype "passive"))
      (node (ref "J3") (pin "2") (pinfunction "S_2") (pintype "passive"))
      (node (ref "J4") (pin "2") (pinfunction "S_2") (pintype "passive"))
      (node (ref "X1") (pin "2") (pinfunction "KL_2") (pintype "passive"))
    )
    (net (code "120") (name "VCC_SERVO_12V") (class "Default")
      (node (ref "C5") (pin "+") (pinfunction "+_+") (pintype "passive"))
      (node (ref "C6") (pin "1") (pinfunction "1_1") (pintype "passive"))
      (node (ref "F2") (pin "1") (pinfunction "1_1") (pintype "passive"))
      (node (ref "J5") (pin "2") (pinfunction "S_2") (pintype "passive"))
      (node (ref "X2") (pin "2") (pinfunction "KL_2") (pintype "passive"))
    )
    (net (code "121") (name "unconnected-(IC7-AIO-Pad27)") (class "Default")
      (node (ref "IC7") (pin "27") (pinfunction "AIO_27") (pintype "passive"))
    )
    (net (code "122") (name "unconnected-(IC7-MISO-Pad23)") (class "Default")
      (node (ref "IC7") (pin "23") (pinfunction "MISO_23") (pintype "passive"))
    )
    (net (code "123") (name "unconnected-(IC7-MOSI-Pad24)") (class "Default")
      (node (ref "IC7") (pin "24") (pinfunction "MOSI_24") (pintype "passive"))
    )
    (net (code "124") (name "unconnected-(IC7-NCSB-Pad21)") (class "Default")
      (node (ref "IC7") (pin "21") (pinfunction "NCSB_21") (pintype "passive"))
    )
    (net (code "125") (name "unconnected-(IC7-PCMC-Pad12)") (class "Default")
      (node (ref "IC7") (pin "12") (pinfunction "PCMC_12") (pintype "passive"))
    )
    (net (code "126") (name "unconnected-(IC7-PCMI-Pad11)") (class "Default")
      (node (ref "IC7") (pin "11") (pinfunction "PCMI_11") (pintype "passive"))
    )
    (net (code "127") (name "unconnected-(IC7-PCMO-Pad7)") (class "Default")
      (node (ref "IC7") (pin "7") (pinfunction "PCMO_7") (pintype "passive"))
    )
    (net (code "128") (name "unconnected-(IC7-PCMS-Pad13)") (class "Default")
      (node (ref "IC7") (pin "13") (pinfunction "PCMS_13") (pintype "passive"))
    )
    (net (code "129") (name "unconnected-(IC7-PIO2-Pad3)") (class "Default")
      (node (ref "IC7") (pin "3") (pinfunction "PIO2_3") (pintype "passive"))
    )
    (net (code "130") (name "unconnected-(IC7-PIO3-Pad4)") (class "Default")
      (node (ref "IC7") (pin "4") (pinfunction "PIO3_4") (pintype "passive"))
    )
    (net (code "131") (name "unconnected-(IC7-PIO5-Pad25)") (class "Default")
      (node (ref "IC7") (pin "25") (pinfunction "PIO5_25") (pintype "passive"))
    )
    (net (code "132") (name "unconnected-(IC7-PIO6-Pad18)") (class "Default")
      (node (ref "IC7") (pin "18") (pinfunction "PIO6_18") (pintype "passive"))
    )
    (net (code "133") (name "unconnected-(IC7-SCLK-Pad22)") (class "Default")
      (node (ref "IC7") (pin "22") (pinfunction "SCLK_22") (pintype "passive"))
    )
    (net (code "134") (name "unconnected-(IC7-USB_D+-Pad8)") (class "Default")
      (node (ref "IC7") (pin "8") (pinfunction "USB_D+_8") (pintype "passive"))
    )
    (net (code "135") (name "unconnected-(IC7-USB_D--Pad9)") (class "Default")
      (node (ref "IC7") (pin "9") (pinfunction "USB_D-_9") (pintype "passive"))
    )
    (net (code "136") (name "unconnected-(IC8A-R2OUT-Pad9)") (class "Default")
      (node (ref "IC8") (pin "9") (pinfunction "R2OUT_9") (pintype "output"))
    )
    (net (code "137") (name "unconnected-(IC8A-T2OUT-Pad7)") (class "Default")
      (node (ref "IC8") (pin "7") (pinfunction "T2OUT_7") (pintype "output"))
    )
    (net (code "138") (name "unconnected-(IC9-INT-Pad6)") (class "Default")
      (node (ref "IC9") (pin "6") (pinfunction "INT_6") (pintype "bidirectional"))
    )
    (net (code "139") (name "unconnected-(IC9-TP-Pad10)") (class "Default")
      (node (ref "IC9") (pin "10") (pinfunction "TP_10") (pintype "bidirectional"))
    )
    (net (code "140") (name "unconnected-(SV1-Pad8)") (class "Default")
      (node (ref "SV1") (pin "8") (pinfunction "8_8") (pintype "passive"))
    )
  )
)
